# Spine14v1.net
KiCad netlist of a schematic drawn in EAGLE
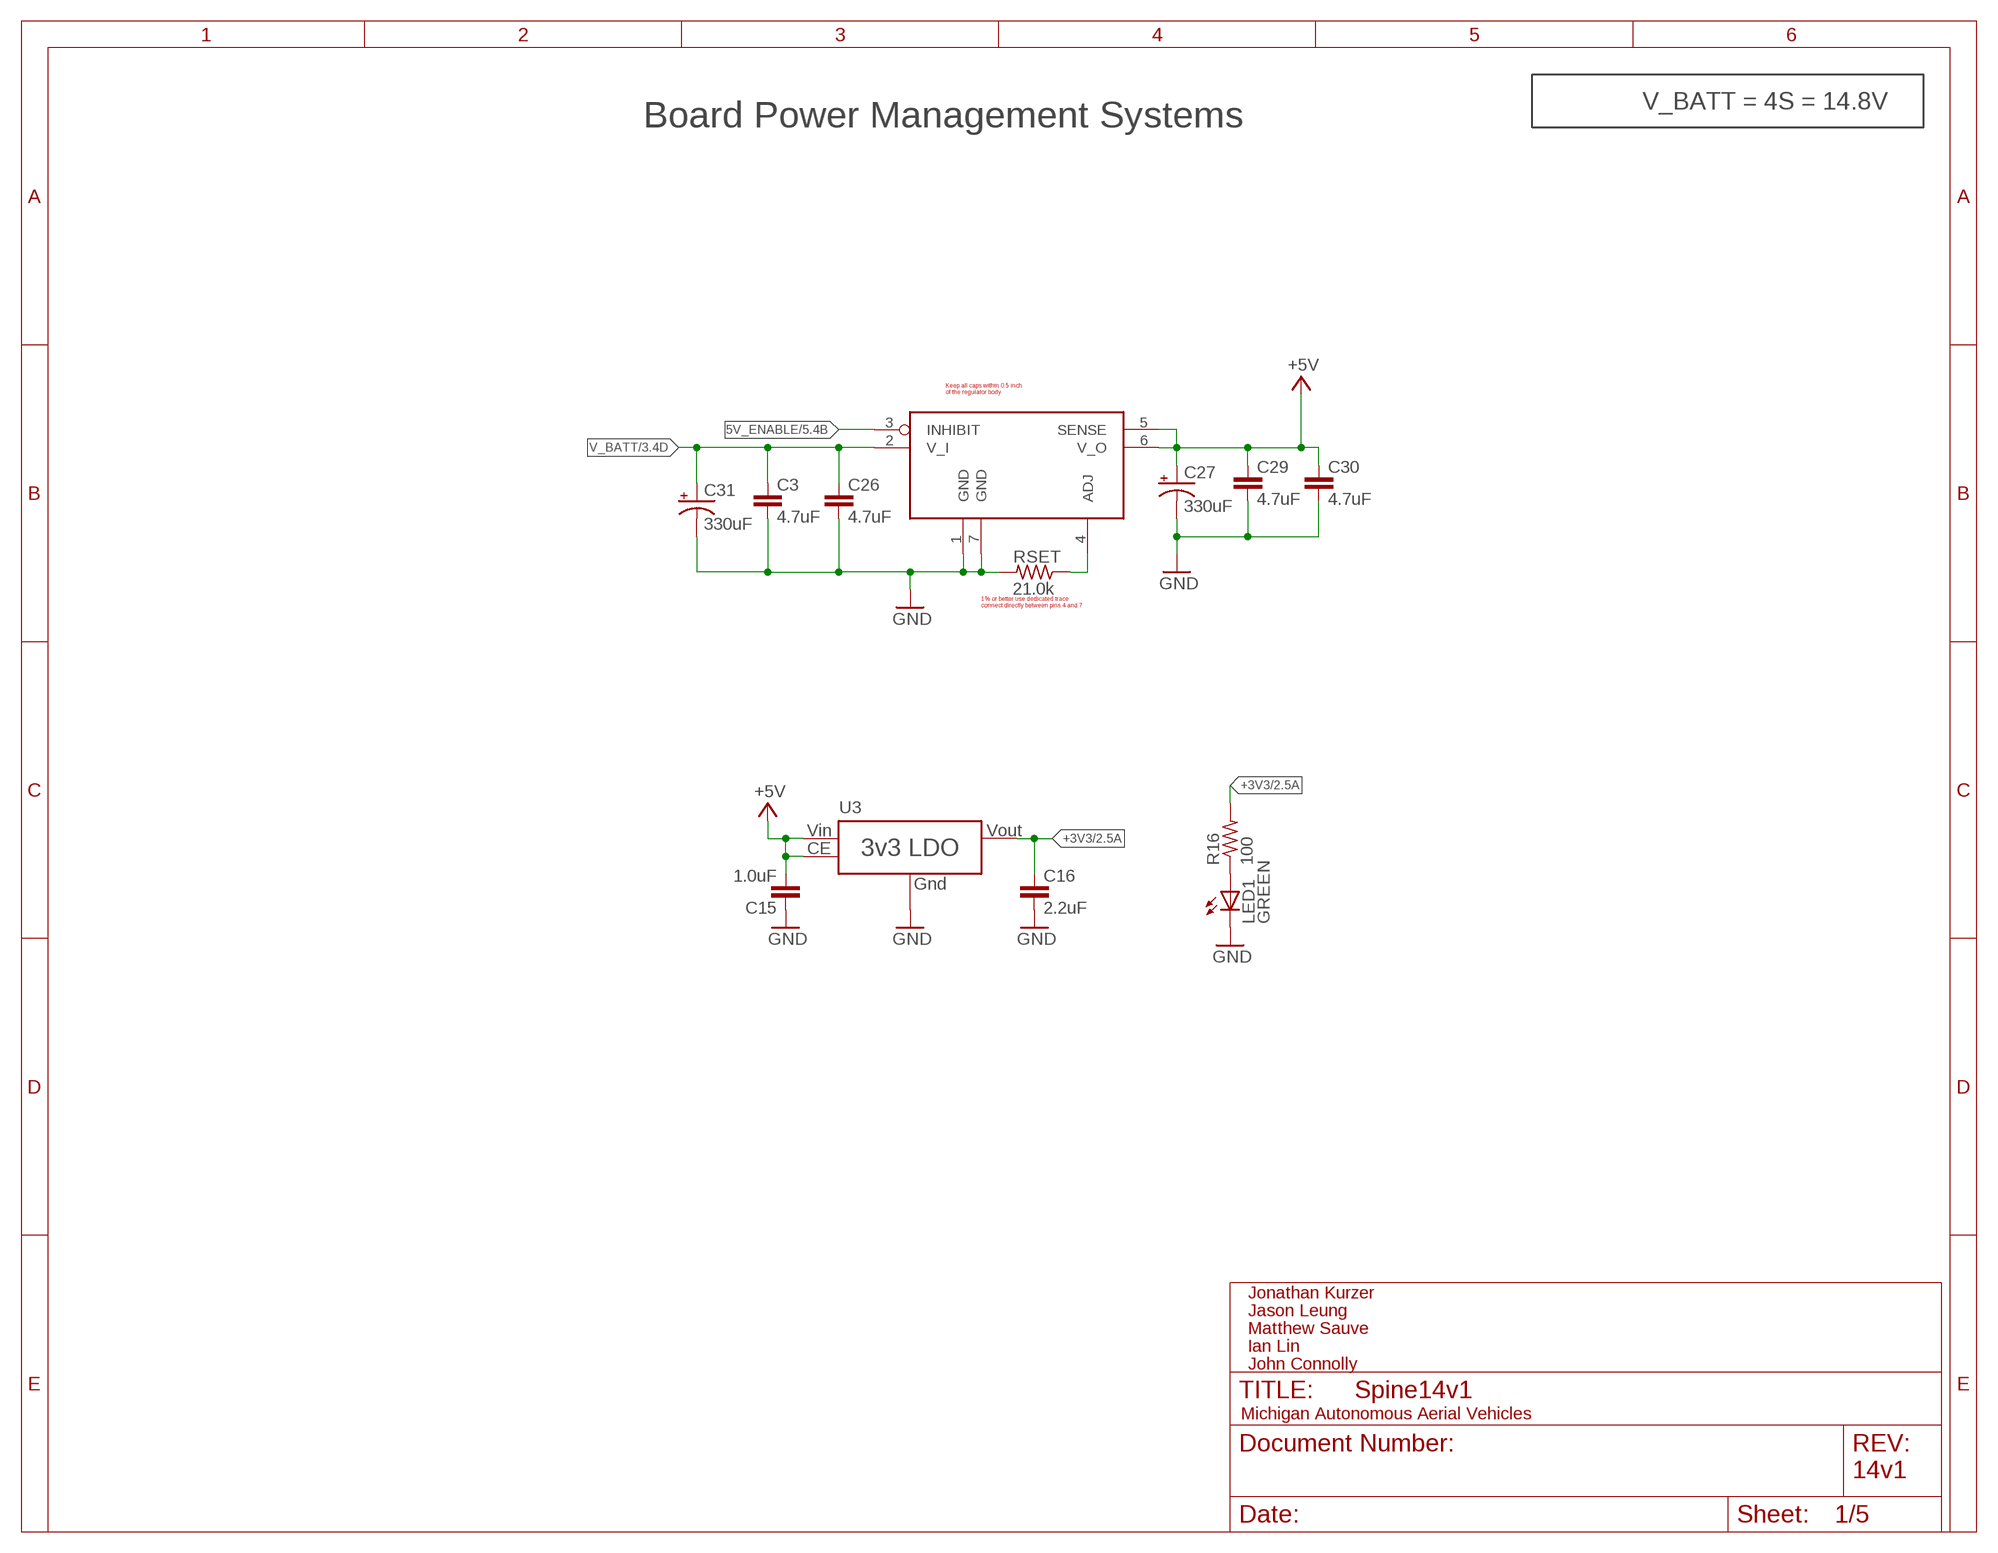
[diagram p0: schematic, sheet 1]
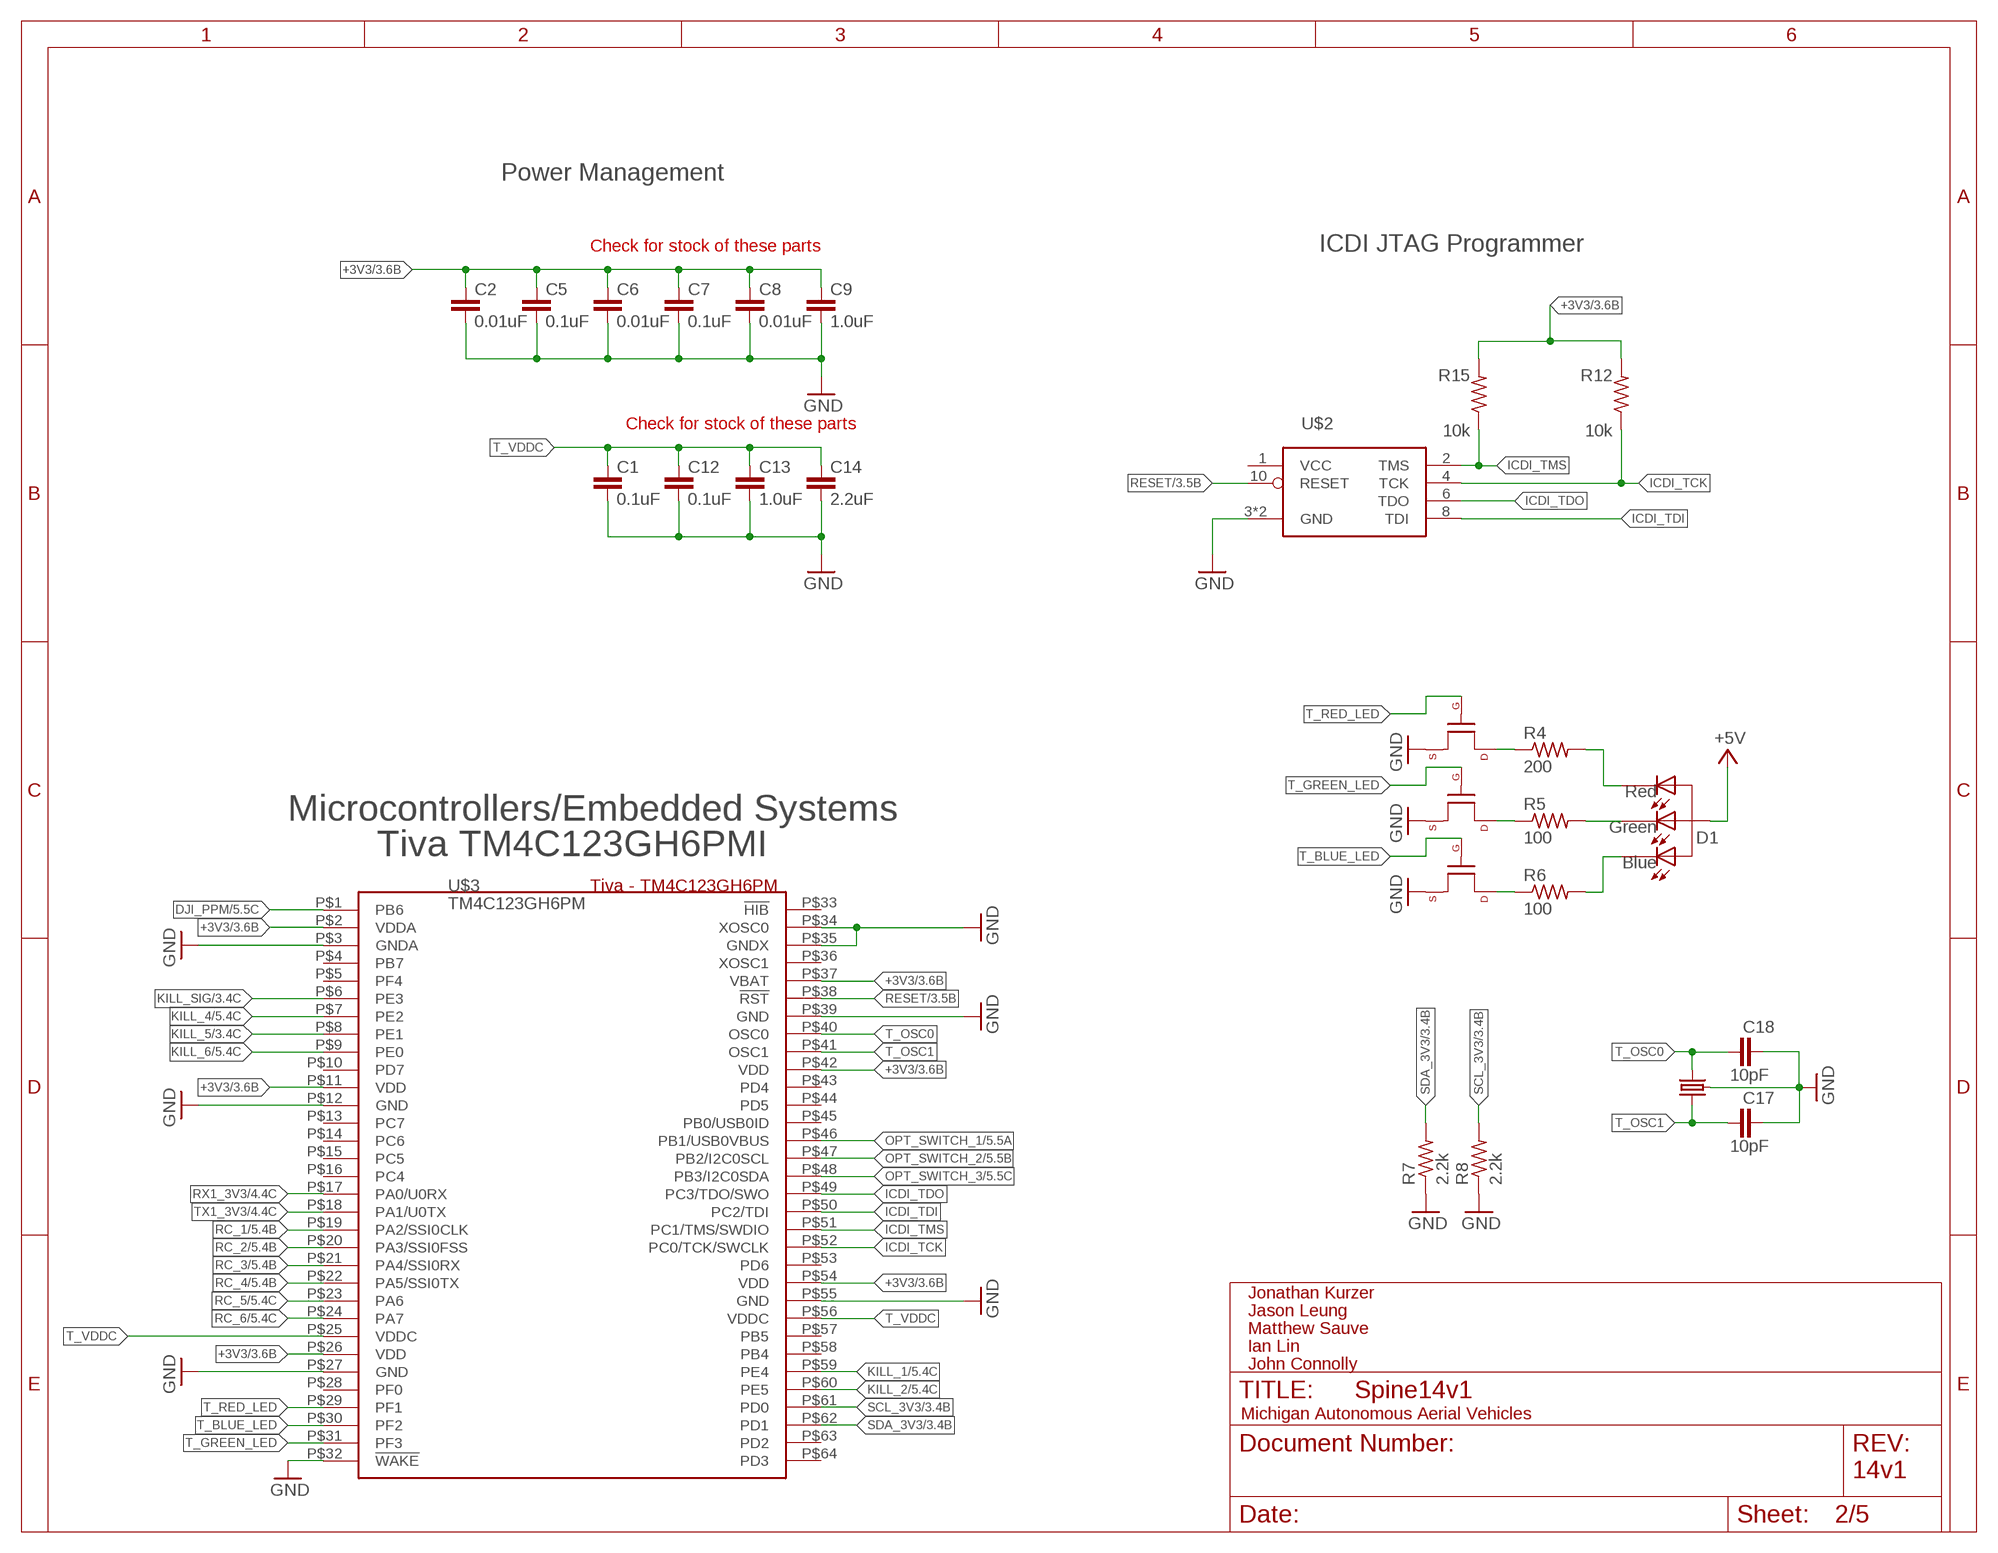
[diagram p1: schematic, sheet 2]
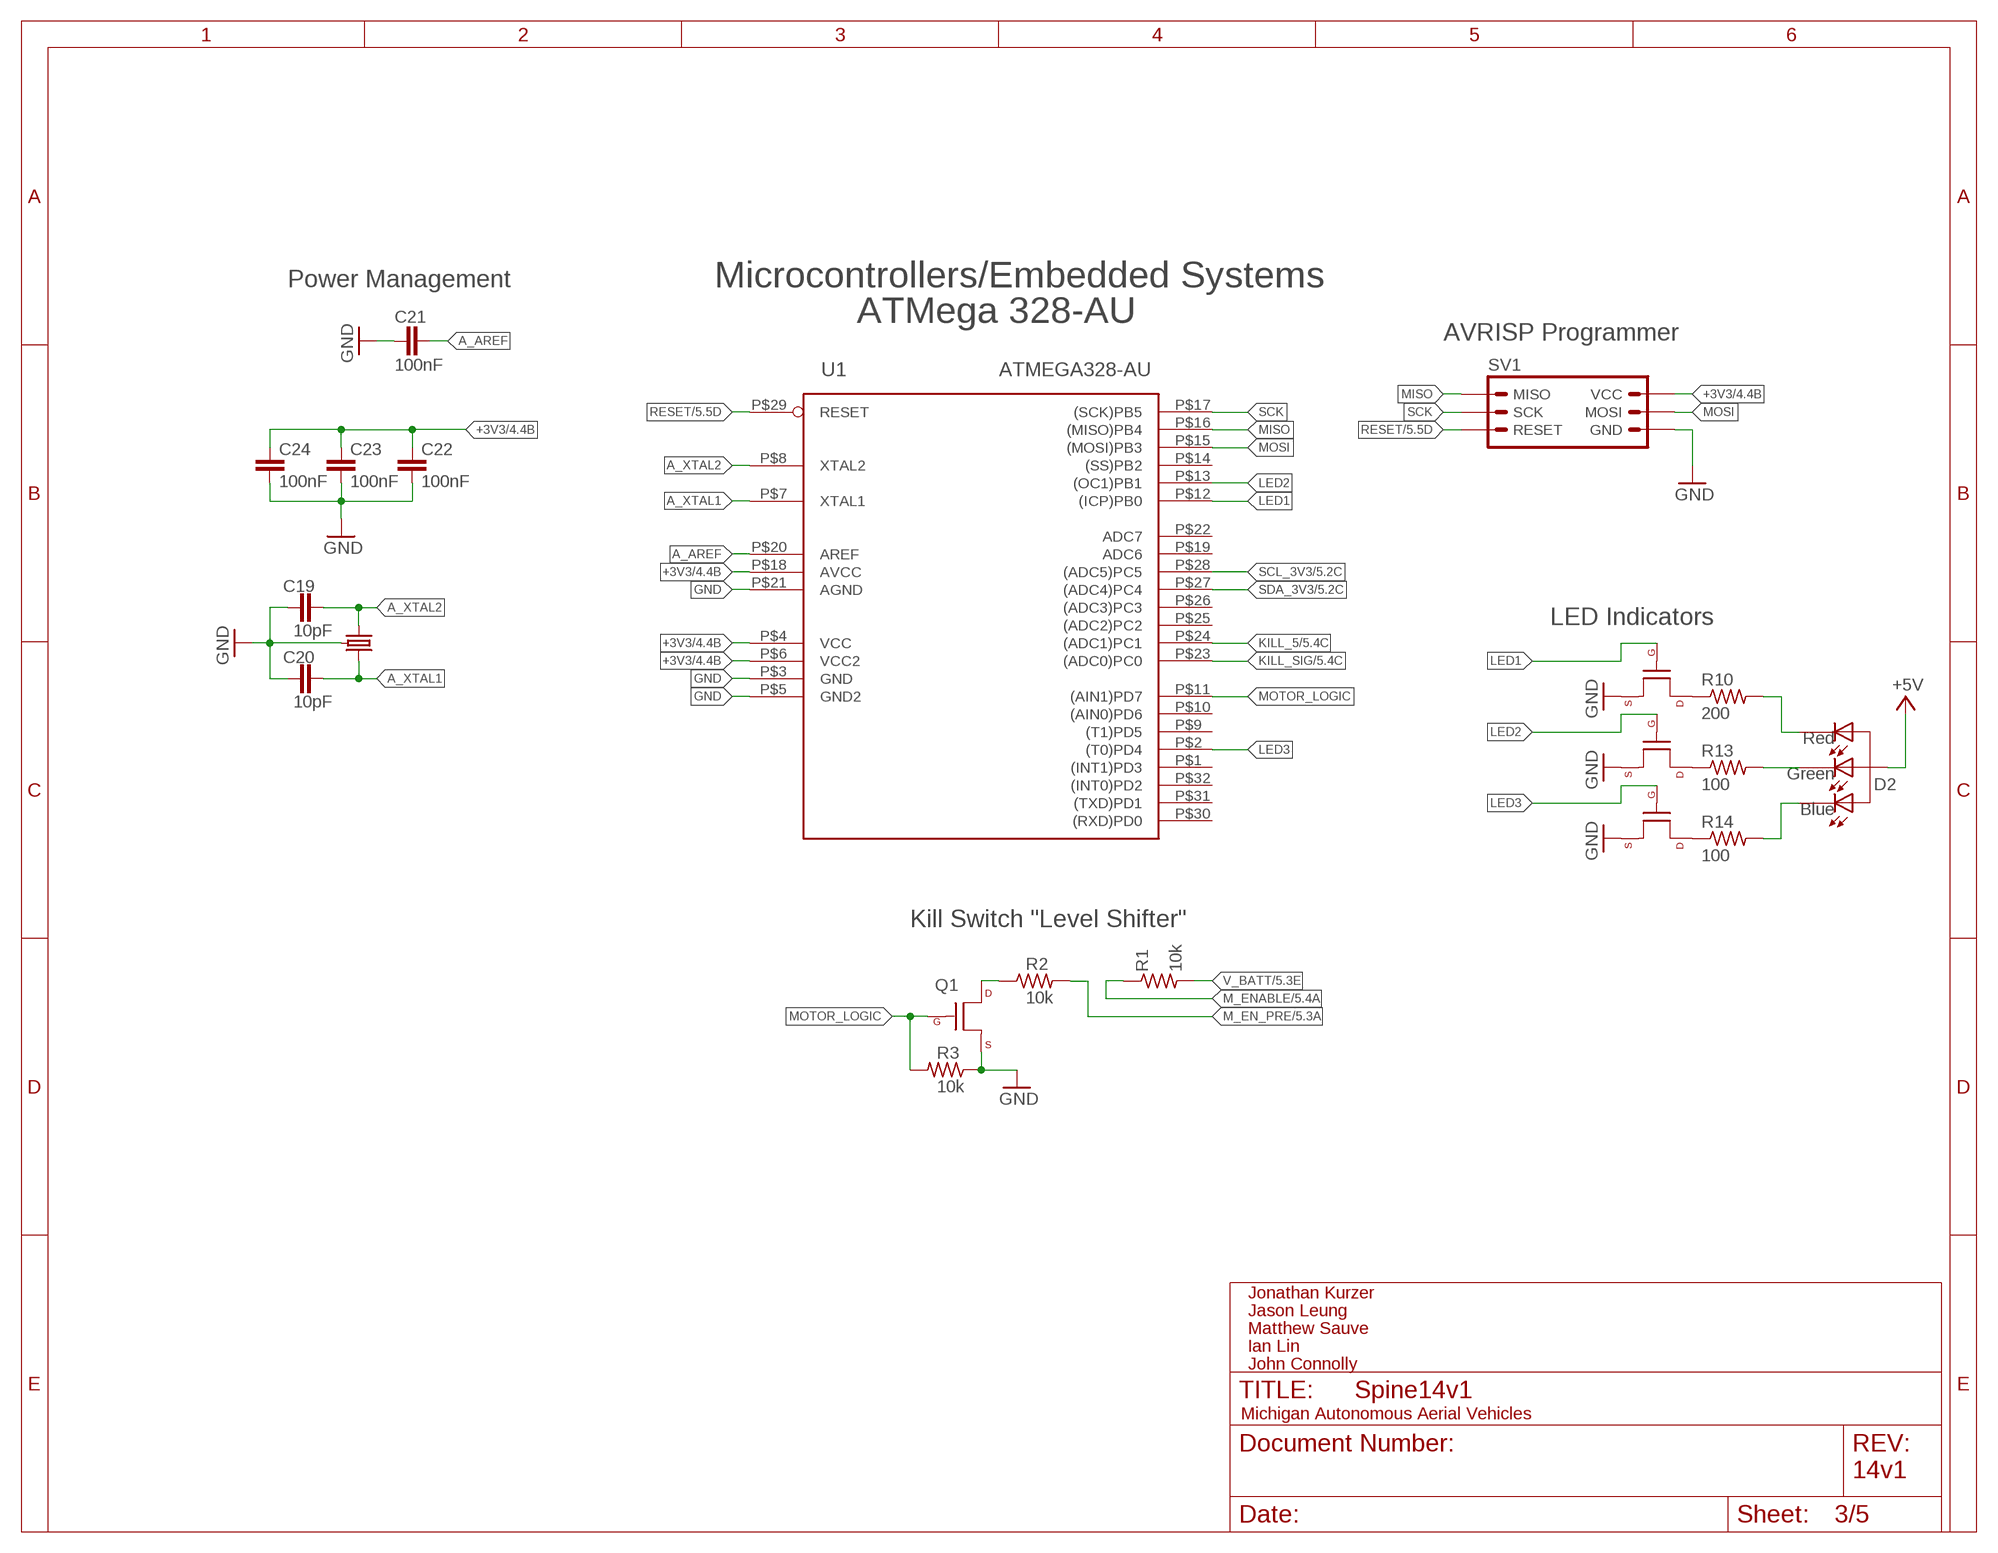
[diagram p2: schematic, sheet 3]
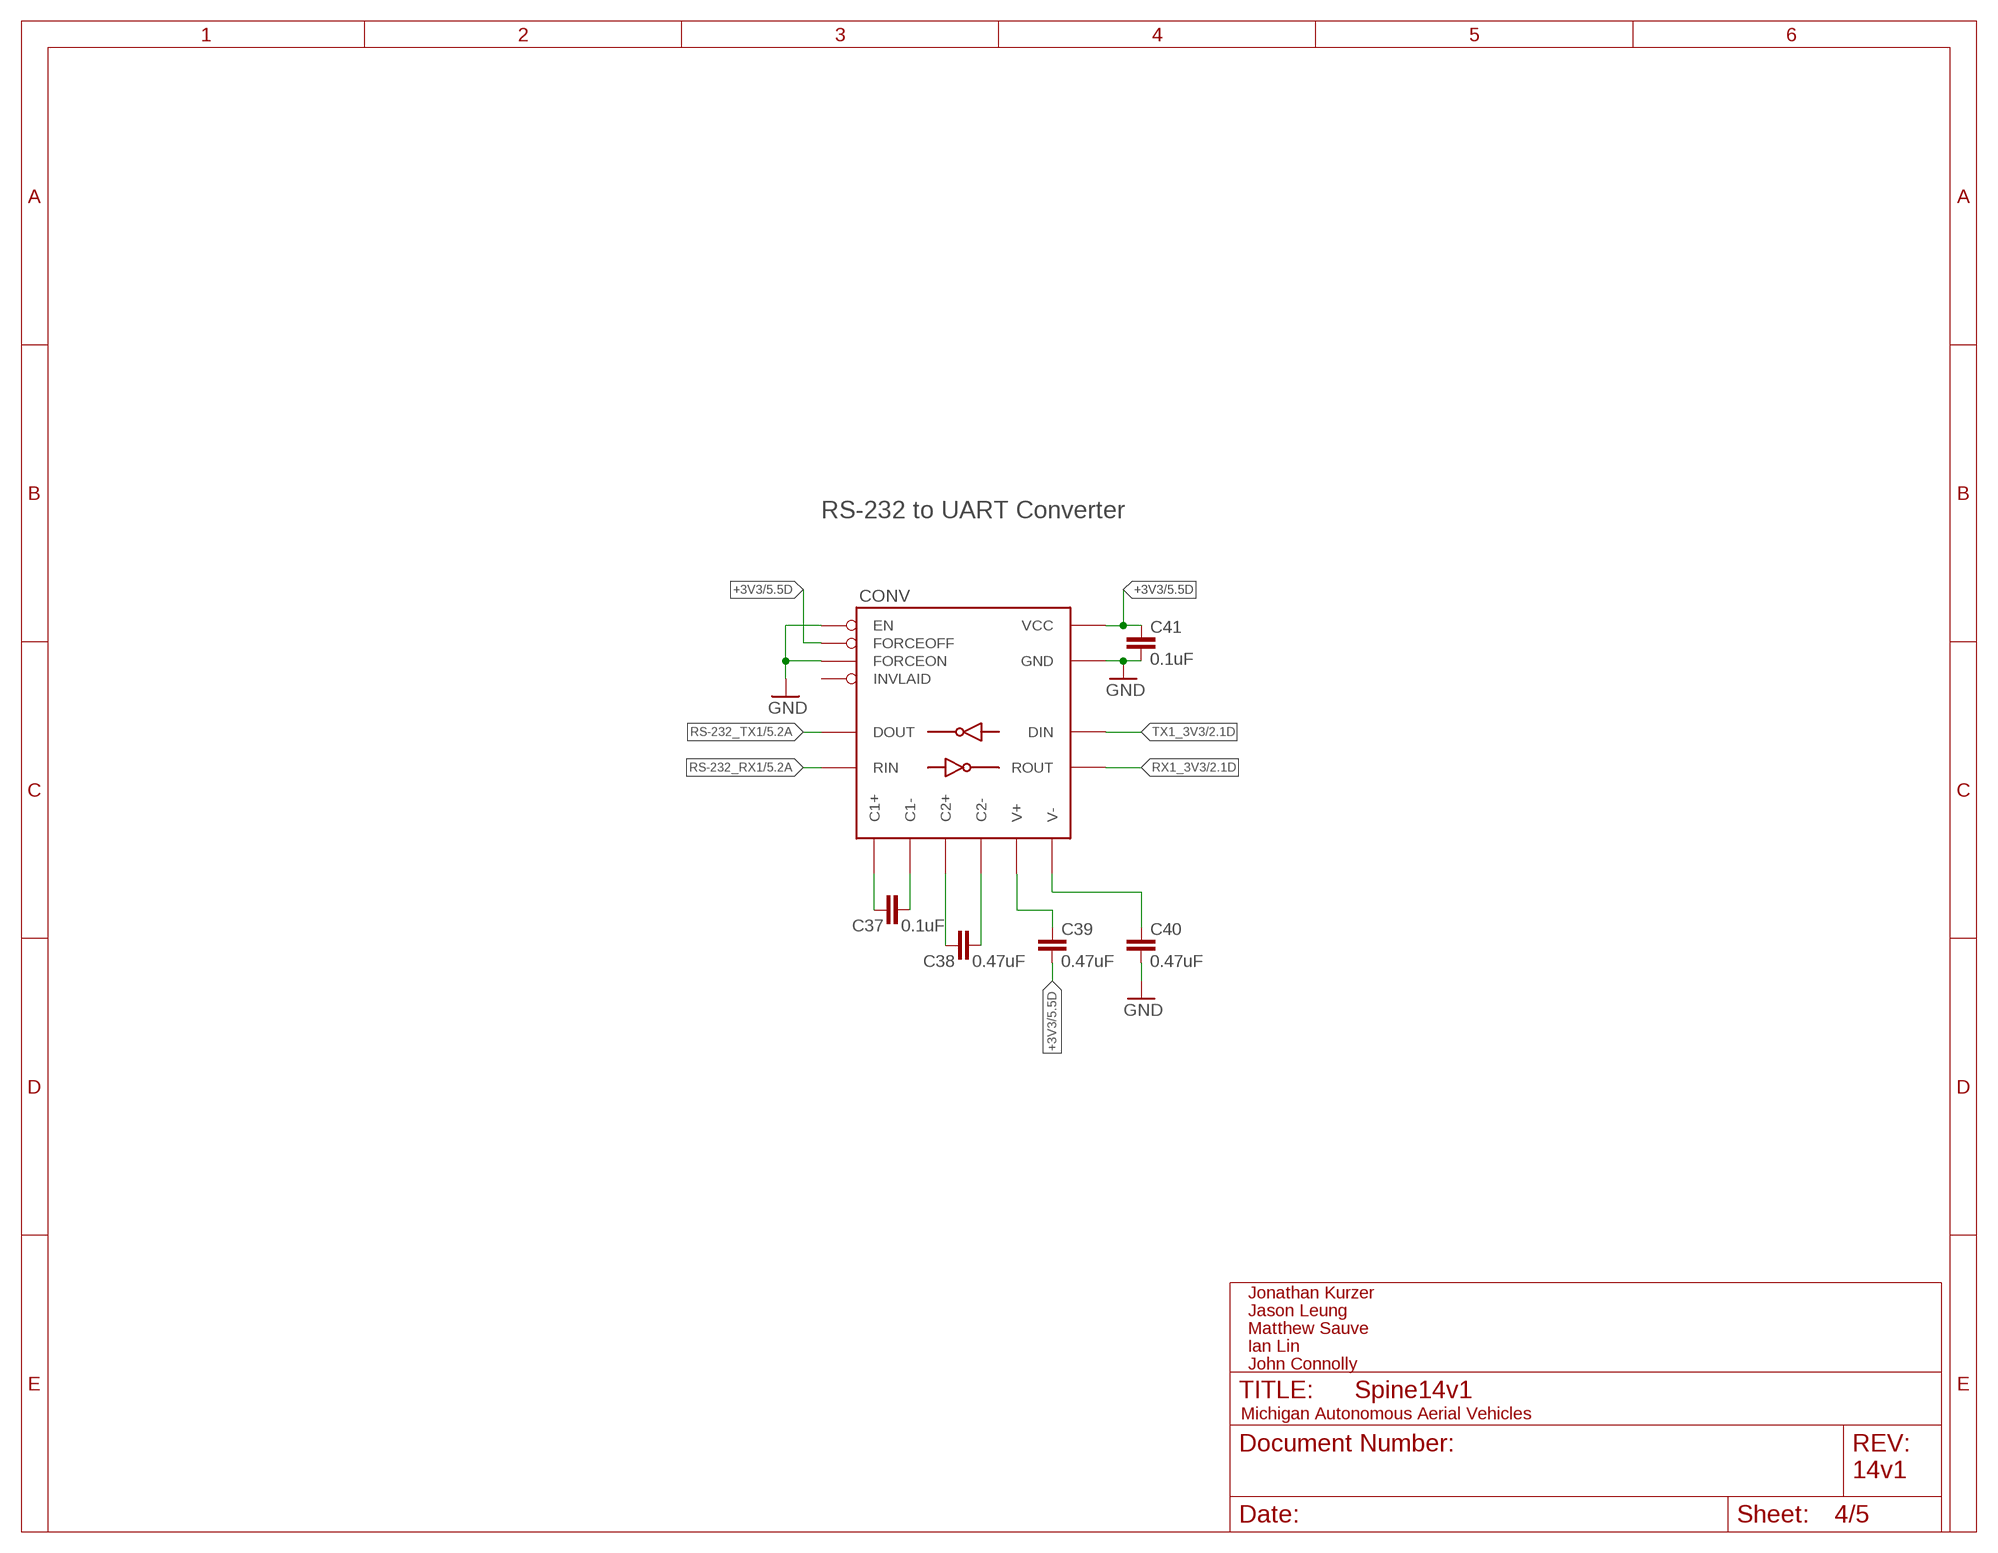
[diagram p3: schematic, sheet 4]
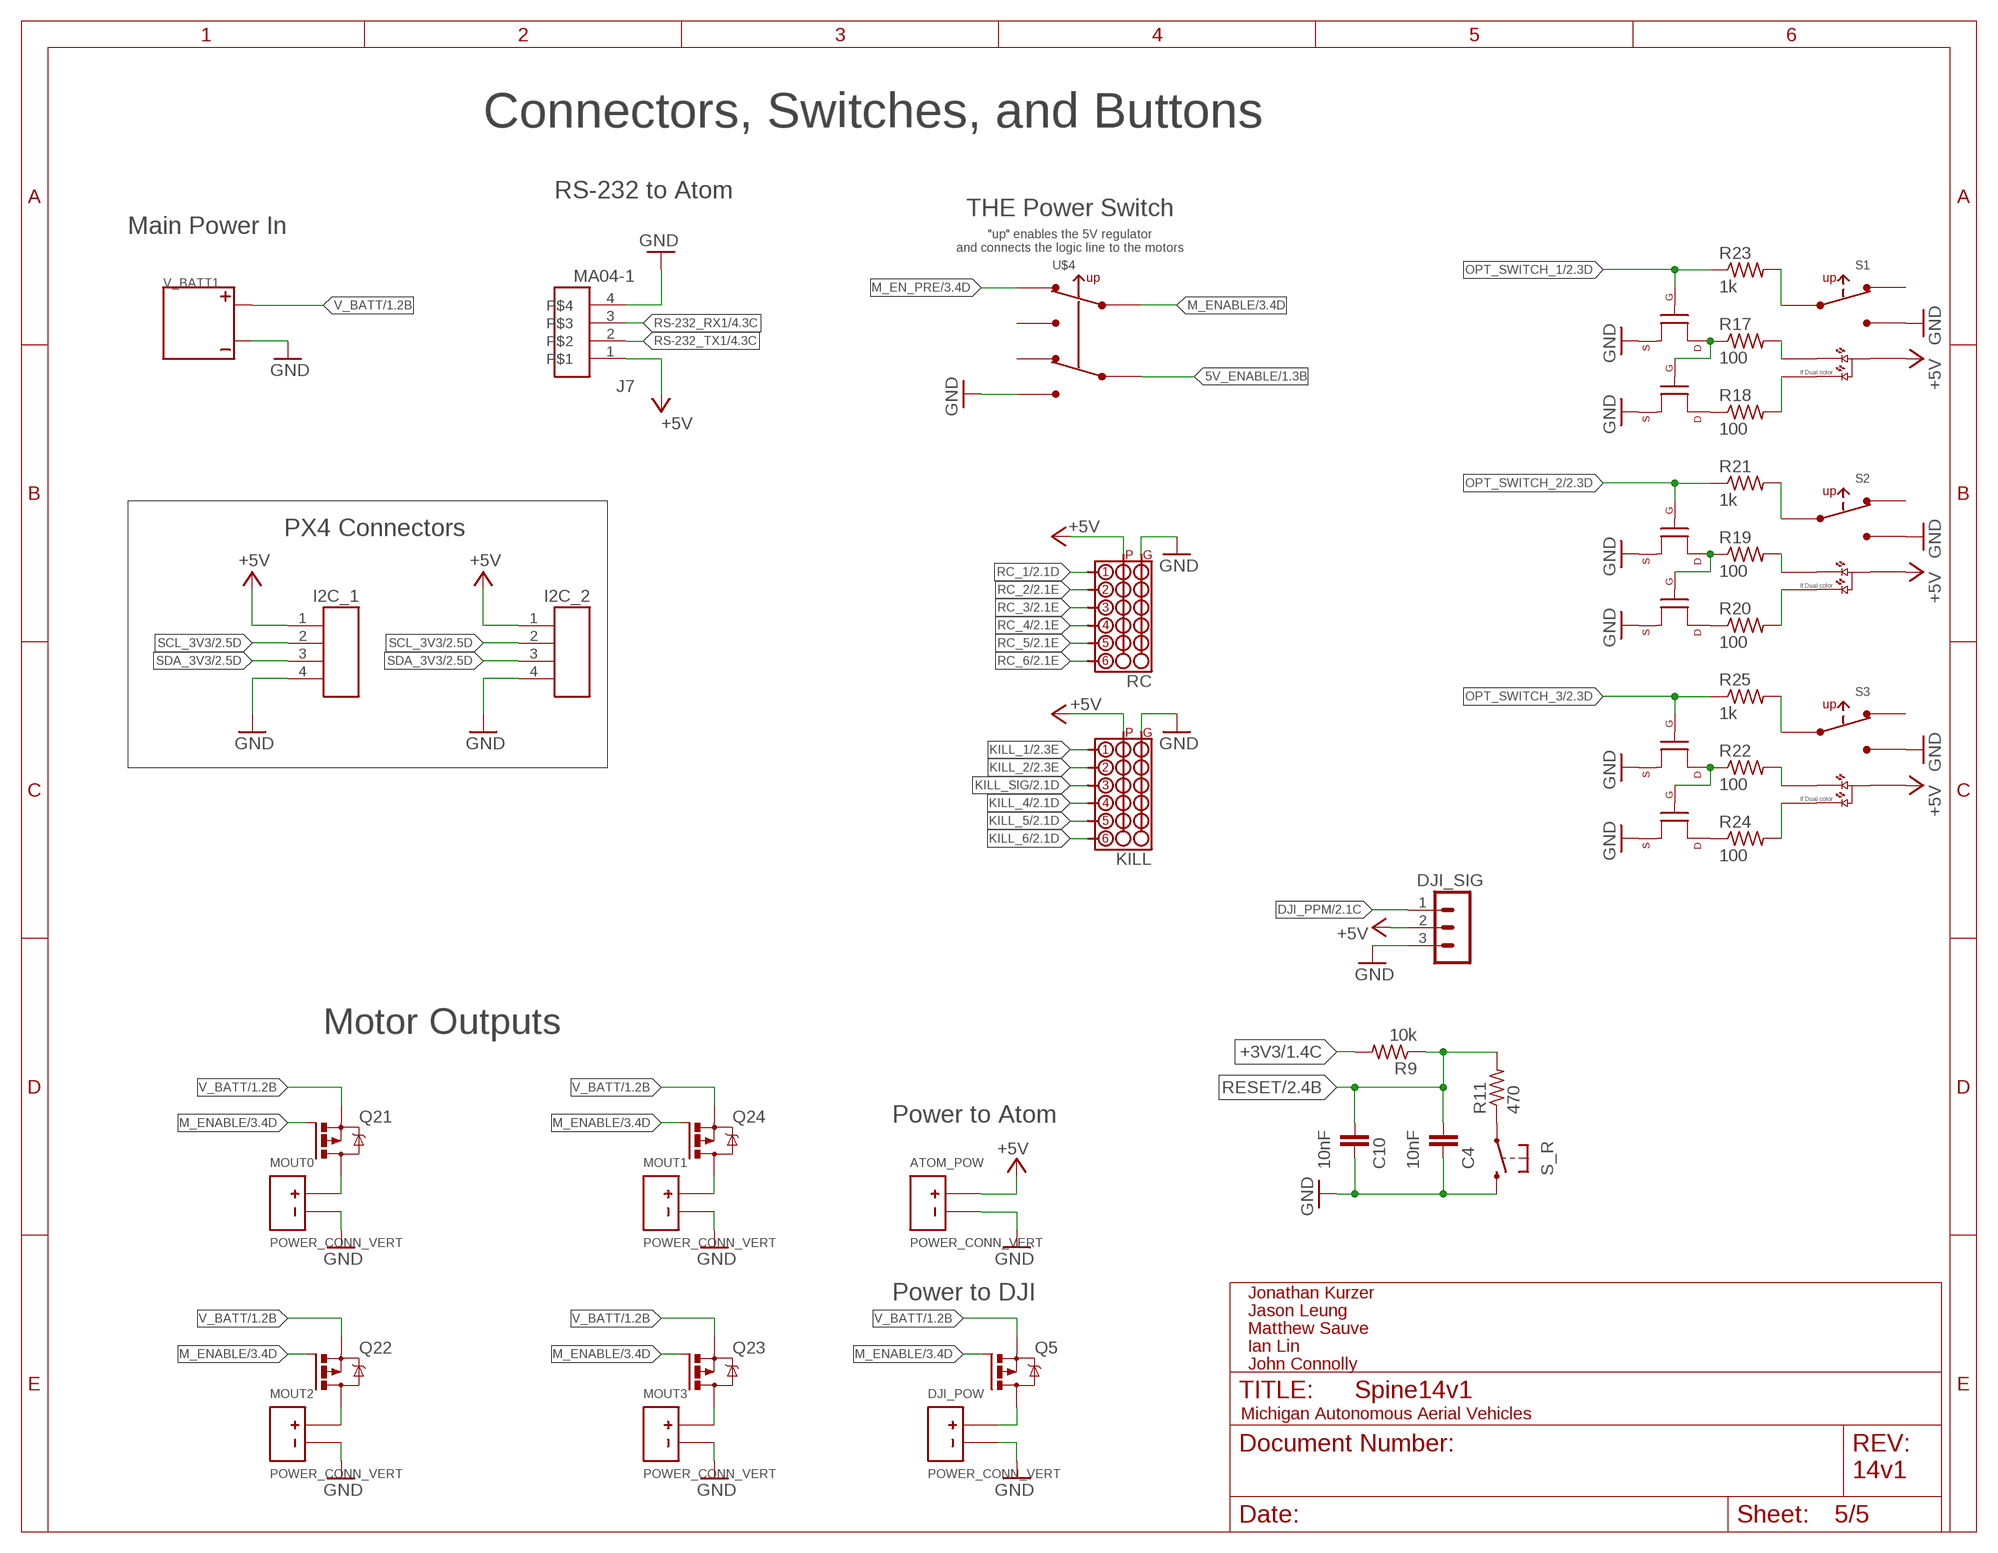
[diagram p4: schematic, sheet 5]

(export (version "E")
  (design (tool "Eeschema 10.0.6"))
  (components
    (comp (ref "C19")
      (value "10pF")
      (footprint "eagle-import:C0603")
      (fields (field (name "DIGIKEY#") "399-1049-1-ND"))
      (libsource (lib "eagle-import") (part "C-EUC0603"))
    )
    (comp (ref "C20")
      (value "10pF")
      (footprint "eagle-import:C0603")
      (fields (field (name "DIGIKEY#") "399-1049-1-ND"))
      (libsource (lib "eagle-import") (part "C-EUC0603"))
    )
    (comp (ref "C21")
      (value "100nF")
      (footprint "eagle-import:C0603")
      (fields (field (name "DIGIKEY#") "1276-1000-1-ND"))
      (libsource (lib "eagle-import") (part "C-EUC0603"))
    )
    (comp (ref "C22")
      (value "100nF")
      (footprint "eagle-import:C0603")
      (fields (field (name "DIGIKEY#") "1276-1000-1-ND"))
      (libsource (lib "eagle-import") (part "C-EUC0603"))
    )
    (comp (ref "C23")
      (value "100nF")
      (footprint "eagle-import:C0603")
      (fields (field (name "DIGIKEY#") "1276-1000-1-ND"))
      (libsource (lib "eagle-import") (part "C-EUC0603"))
    )
    (comp (ref "C24")
      (value "100nF")
      (footprint "eagle-import:C0603")
      (fields (field (name "DIGIKEY#") "1276-1000-1-ND"))
      (libsource (lib "eagle-import") (part "C-EUC0603"))
    )
    (comp (ref "D2")
      (value "LED_RGB_CA")
      (footprint "eagle-import:LED_RGB_0606")
      (libsource (lib "eagle-import") (part "LED_RGB_CA"))
    )
    (comp (ref "Q1")
      (value "MOSFET-NCHANNELSMD")
      (footprint "eagle-import:SOT23-3")
      (libsource (lib "eagle-import") (part "MOSFET-NCHANNELSMD"))
    )
    (comp (ref "Q6")
      (value "MOSFET-NCHANNELSMD")
      (footprint "eagle-import:SOT23-3")
      (libsource (lib "eagle-import") (part "MOSFET-NCHANNELSMD"))
    )
    (comp (ref "Q7")
      (value "MOSFET-NCHANNELSMD")
      (footprint "eagle-import:SOT23-3")
      (libsource (lib "eagle-import") (part "MOSFET-NCHANNELSMD"))
    )
    (comp (ref "Q8")
      (value "MOSFET-NCHANNELSMD")
      (footprint "eagle-import:SOT23-3")
      (libsource (lib "eagle-import") (part "MOSFET-NCHANNELSMD"))
    )
    (comp (ref "R1")
      (value "10k")
      (footprint "eagle-import:R0603")
      (libsource (lib "eagle-import") (part "R-USR0603"))
    )
    (comp (ref "R2")
      (value "10k")
      (footprint "eagle-import:R0603")
      (libsource (lib "eagle-import") (part "R-USR0603"))
    )
    (comp (ref "R3")
      (value "10k")
      (footprint "eagle-import:R0603")
      (libsource (lib "eagle-import") (part "R-USR0603"))
    )
    (comp (ref "R10")
      (value "200")
      (footprint "eagle-import:R0603")
      (libsource (lib "eagle-import") (part "R-USR0603"))
    )
    (comp (ref "R13")
      (value "100")
      (footprint "eagle-import:R0603")
      (libsource (lib "eagle-import") (part "R-USR0603"))
    )
    (comp (ref "R14")
      (value "100")
      (footprint "eagle-import:R0603")
      (libsource (lib "eagle-import") (part "R-USR0603"))
    )
    (comp (ref "SV1")
      (value "AVRISP-6_3X2_PLUG_OF_NAILS")
      (footprint "eagle-import:TC2030-IDC")
      (libsource (lib "eagle-import") (part "AVRISP-6_3X2_PLUG_OF_NAILS"))
    )
    (comp (ref "U$6")
      (value "CRYSTAL_403C11E16")
      (footprint "eagle-import:4-SMD-SWITCH")
      (libsource (lib "eagle-import") (part "CRYSTAL_403C11E16"))
    )
    (comp (ref "U1")
      (value "ATMEGA328-AU")
      (footprint "eagle-import:32-TQFP")
      (libsource (lib "eagle-import") (part "ATMEGA328-AU"))
    )
    (comp (ref "ATOM_POW")
      (value "POWER_CONN_VERT")
      (footprint "eagle-import:POWER_CONN")
      (libsource (lib "eagle-import") (part "POWER_CONN_VERT"))
    )
    (comp (ref "C4")
      (value "10nF")
      (footprint "eagle-import:C0603")
      (libsource (lib "eagle-import") (part "C-EUC0603"))
    )
    (comp (ref "C10")
      (value "10nF")
      (footprint "eagle-import:C0603")
      (libsource (lib "eagle-import") (part "C-EUC0603"))
    )
    (comp (ref "DJI_POW")
      (value "POWER_CONN_VERT")
      (footprint "eagle-import:POWER_CONN")
      (libsource (lib "eagle-import") (part "POWER_CONN_VERT"))
    )
    (comp (ref "DJI_SIG")
      (value "MA03-1")
      (footprint "eagle-import:MA03-1")
      (libsource (lib "eagle-import") (part "MA03-1"))
    )
    (comp (ref "I2C_1")
      (value "CONN_HEADER_4POS_RIGHT_ANGLE_I2C")
      (footprint "eagle-import:CONN_HEADER_4POS_1.25MM_SMD")
      (libsource (lib "eagle-import") (part "CONN_HEADER_4POS_RIGHT_ANGLE_I2C"))
    )
    (comp (ref "I2C_2")
      (value "CONN_HEADER_4POS_RIGHT_ANGLE_I2C")
      (footprint "eagle-import:CONN_HEADER_4POS_1.25MM_SMD")
      (libsource (lib "eagle-import") (part "CONN_HEADER_4POS_RIGHT_ANGLE_I2C"))
    )
    (comp (ref "J7")
      (value "MA04-1")
      (footprint "eagle-import:MA-04-SMD")
      (libsource (lib "eagle-import") (part "MA04-1"))
    )
    (comp (ref "KILL")
      (value "RC_RECIEVER_RECEP")
      (footprint "eagle-import:RC_RECIEVER_RECEP")
      (libsource (lib "eagle-import") (part "RC_RECIEVER_RECEP"))
    )
    (comp (ref "MOUT0")
      (value "POWER_CONN_VERT")
      (footprint "eagle-import:POWER_CONN")
      (libsource (lib "eagle-import") (part "POWER_CONN_VERT"))
    )
    (comp (ref "MOUT1")
      (value "POWER_CONN_VERT")
      (footprint "eagle-import:POWER_CONN")
      (libsource (lib "eagle-import") (part "POWER_CONN_VERT"))
    )
    (comp (ref "MOUT2")
      (value "POWER_CONN_VERT")
      (footprint "eagle-import:POWER_CONN")
      (libsource (lib "eagle-import") (part "POWER_CONN_VERT"))
    )
    (comp (ref "MOUT3")
      (value "POWER_CONN_VERT")
      (footprint "eagle-import:POWER_CONN")
      (libsource (lib "eagle-import") (part "POWER_CONN_VERT"))
    )
    (comp (ref "Q5")
      (value "P-MOSFET-SO8POWER-PAK")
      (footprint "eagle-import:SO-8_POWER-PAK")
      (libsource (lib "eagle-import") (part "P-MOSFET-SO8POWER-PAK"))
    )
    (comp (ref "Q9")
      (value "MOSFET-NCHANNELSMD")
      (footprint "eagle-import:SOT23-3")
      (libsource (lib "eagle-import") (part "MOSFET-NCHANNELSMD"))
    )
    (comp (ref "Q10")
      (value "MOSFET-NCHANNELSMD")
      (footprint "eagle-import:SOT23-3")
      (libsource (lib "eagle-import") (part "MOSFET-NCHANNELSMD"))
    )
    (comp (ref "Q11")
      (value "MOSFET-NCHANNELSMD")
      (footprint "eagle-import:SOT23-3")
      (libsource (lib "eagle-import") (part "MOSFET-NCHANNELSMD"))
    )
    (comp (ref "Q12")
      (value "MOSFET-NCHANNELSMD")
      (footprint "eagle-import:SOT23-3")
      (libsource (lib "eagle-import") (part "MOSFET-NCHANNELSMD"))
    )
    (comp (ref "Q13")
      (value "MOSFET-NCHANNELSMD")
      (footprint "eagle-import:SOT23-3")
      (libsource (lib "eagle-import") (part "MOSFET-NCHANNELSMD"))
    )
    (comp (ref "Q14")
      (value "MOSFET-NCHANNELSMD")
      (footprint "eagle-import:SOT23-3")
      (libsource (lib "eagle-import") (part "MOSFET-NCHANNELSMD"))
    )
    (comp (ref "Q21")
      (value "P-MOSFET-SO8POWER-PAK")
      (footprint "eagle-import:SO-8_POWER-PAK")
      (libsource (lib "eagle-import") (part "P-MOSFET-SO8POWER-PAK"))
    )
    (comp (ref "Q22")
      (value "P-MOSFET-SO8POWER-PAK")
      (footprint "eagle-import:SO-8_POWER-PAK")
      (libsource (lib "eagle-import") (part "P-MOSFET-SO8POWER-PAK"))
    )
    (comp (ref "Q23")
      (value "P-MOSFET-SO8POWER-PAK")
      (footprint "eagle-import:SO-8_POWER-PAK")
      (libsource (lib "eagle-import") (part "P-MOSFET-SO8POWER-PAK"))
    )
    (comp (ref "Q24")
      (value "P-MOSFET-SO8POWER-PAK")
      (footprint "eagle-import:SO-8_POWER-PAK")
      (libsource (lib "eagle-import") (part "P-MOSFET-SO8POWER-PAK"))
    )
    (comp (ref "R9")
      (value "10k")
      (footprint "eagle-import:R0603")
      (libsource (lib "eagle-import") (part "R-USR0603"))
    )
    (comp (ref "R11")
      (value "470")
      (footprint "eagle-import:R0603")
      (libsource (lib "eagle-import") (part "R-USR0603"))
    )
    (comp (ref "R17")
      (value "100")
      (footprint "eagle-import:R0603")
      (libsource (lib "eagle-import") (part "R-USR0603"))
    )
    (comp (ref "R18")
      (value "100")
      (footprint "eagle-import:R0603")
      (libsource (lib "eagle-import") (part "R-USR0603"))
    )
    (comp (ref "R19")
      (value "100")
      (footprint "eagle-import:R0603")
      (libsource (lib "eagle-import") (part "R-USR0603"))
    )
    (comp (ref "R20")
      (value "100")
      (footprint "eagle-import:R0603")
      (libsource (lib "eagle-import") (part "R-USR0603"))
    )
    (comp (ref "R21")
      (value "1k")
      (footprint "eagle-import:R0603")
      (libsource (lib "eagle-import") (part "R-USR0603"))
    )
    (comp (ref "R22")
      (value "100")
      (footprint "eagle-import:R0603")
      (libsource (lib "eagle-import") (part "R-USR0603"))
    )
    (comp (ref "R23")
      (value "1k")
      (footprint "eagle-import:R0603")
      (libsource (lib "eagle-import") (part "R-USR0603"))
    )
    (comp (ref "R24")
      (value "100")
      (footprint "eagle-import:R0603")
      (libsource (lib "eagle-import") (part "R-USR0603"))
    )
    (comp (ref "R25")
      (value "1k")
      (footprint "eagle-import:R0603")
      (libsource (lib "eagle-import") (part "R-USR0603"))
    )
    (comp (ref "RC")
      (value "RC_RECIEVER_RECEP")
      (footprint "eagle-import:RC_RECIEVER_RECEP")
      (libsource (lib "eagle-import") (part "RC_RECIEVER_RECEP"))
    )
    (comp (ref "S1")
      (value "SWITCH_SPDT_ILUMINATED_2COLOR_VERT_ILLUMINATED")
      (footprint "eagle-import:NKK_VERT_SWITCH_6PIN")
      (libsource (lib "eagle-import") (part "SWITCH_SPDT_ILUMINATED_2COLOR_VERT_ILLUMINATED"))
    )
    (comp (ref "S2")
      (value "SWITCH_SPDT_ILUMINATED_2COLOR_VERT_ILLUMINATED")
      (footprint "eagle-import:NKK_VERT_SWITCH_6PIN")
      (libsource (lib "eagle-import") (part "SWITCH_SPDT_ILUMINATED_2COLOR_VERT_ILLUMINATED"))
    )
    (comp (ref "S3")
      (value "SWITCH_SPDT_ILUMINATED_2COLOR_VERT_ILLUMINATED")
      (footprint "eagle-import:NKK_VERT_SWITCH_6PIN")
      (libsource (lib "eagle-import") (part "SWITCH_SPDT_ILUMINATED_2COLOR_VERT_ILLUMINATED"))
    )
    (comp (ref "S_R")
      (value "TACT_BUTTONSMD")
      (footprint "eagle-import:TACT-MOM-SMD")
      (libsource (lib "eagle-import") (part "TACT_BUTTONSMD"))
    )
    (comp (ref "U$4")
      (value "JON_LIB_SWITCH_DPDT")
      (footprint "eagle-import:JON_LIB_SWITCH_VERT_DPDT")
      (libsource (lib "eagle-import") (part "JON_LIB_SWITCH_DPDT"))
    )
    (comp (ref "V_BATT1")
      (value "BATT-CONN-50A_MINI-FIT-SR_THRU-HOLE")
      (footprint "eagle-import:BATT-CONN-50A")
      (libsource (lib "eagle-import") (part "BATT-CONN-50A_MINI-FIT-SR_THRU-HOLE"))
    )
    (comp (ref "C3")
      (value "4.7uF")
      (footprint "eagle-import:C1206")
      (fields (field (name "DIGIKEY#") "587-2994-1-ND"))
      (libsource (lib "eagle-import") (part "C-EUC1206"))
    )
    (comp (ref "C15")
      (value "1.0uF")
      (footprint "eagle-import:C0805")
      (libsource (lib "eagle-import") (part "C-EUC0805"))
    )
    (comp (ref "C16")
      (value "2.2uF")
      (footprint "eagle-import:C0805")
      (libsource (lib "eagle-import") (part "C-EUC0805"))
    )
    (comp (ref "C26")
      (value "4.7uF")
      (footprint "eagle-import:C1206")
      (fields (field (name "DIGIKEY#") "587-2994-1-ND"))
      (libsource (lib "eagle-import") (part "C-EUC1206"))
    )
    (comp (ref "C27")
      (value "330uF")
      (footprint "eagle-import:PANASONIC_F")
      (libsource (lib "eagle-import") (part "CPOL-USF"))
    )
    (comp (ref "C29")
      (value "4.7uF")
      (footprint "eagle-import:C1206")
      (fields (field (name "DIGIKEY#") "587-2994-1-ND"))
      (libsource (lib "eagle-import") (part "C-EUC1206"))
    )
    (comp (ref "C30")
      (value "4.7uF")
      (footprint "eagle-import:C1206")
      (fields (field (name "DIGIKEY#") "587-2994-1-ND"))
      (libsource (lib "eagle-import") (part "C-EUC1206"))
    )
    (comp (ref "C31")
      (value "330uF")
      (footprint "eagle-import:PANASONIC_F")
      (libsource (lib "eagle-import") (part "CPOL-USF"))
    )
    (comp (ref "LED1")
      (value "GREEN")
      (footprint "eagle-import:CHIPLED_0603")
      (libsource (lib "eagle-import") (part "LEDCHIPLED_0603"))
    )
    (comp (ref "R16")
      (value "100")
      (footprint "eagle-import:R0603")
      (libsource (lib "eagle-import") (part "R-USR0603"))
    )
    (comp (ref "RSET")
      (value "21.0k")
      (footprint "eagle-import:R0603")
      (libsource (lib "eagle-import") (part "R-USR0603"))
    )
    (comp (ref "U$5")
      (value "POWER-MODULE-TI-6A_SOLDERLESS_TERMINAL")
      (footprint "eagle-import:POWER-MOD-TI-6A-SOLDERLESS-TERMINAL")
      (libsource (lib "eagle-import") (part "POWER-MODULE-TI-6A_SOLDERLESS_TERMINAL"))
    )
    (comp (ref "U3")
      (value "XC6210")
      (footprint "eagle-import:SOT-25")
      (libsource (lib "eagle-import") (part "XC6210"))
    )
    (comp (ref "C1")
      (value "0.1uF")
      (footprint "eagle-import:C0603")
      (libsource (lib "eagle-import") (part "C-EUC0603"))
    )
    (comp (ref "C2")
      (value "0.01uF")
      (footprint "eagle-import:C0603")
      (libsource (lib "eagle-import") (part "C-EUC0603"))
    )
    (comp (ref "C5")
      (value "0.1uF")
      (footprint "eagle-import:C0603")
      (libsource (lib "eagle-import") (part "C-EUC0603"))
    )
    (comp (ref "C6")
      (value "0.01uF")
      (footprint "eagle-import:C0603")
      (libsource (lib "eagle-import") (part "C-EUC0603"))
    )
    (comp (ref "C7")
      (value "0.1uF")
      (footprint "eagle-import:C0603")
      (libsource (lib "eagle-import") (part "C-EUC0603"))
    )
    (comp (ref "C8")
      (value "0.01uF")
      (footprint "eagle-import:C0603")
      (libsource (lib "eagle-import") (part "C-EUC0603"))
    )
    (comp (ref "C9")
      (value "1.0uF")
      (footprint "eagle-import:C0603")
      (libsource (lib "eagle-import") (part "C-EUC0603"))
    )
    (comp (ref "C12")
      (value "0.1uF")
      (footprint "eagle-import:C0603")
      (libsource (lib "eagle-import") (part "C-EUC0603"))
    )
    (comp (ref "C13")
      (value "1.0uF")
      (footprint "eagle-import:C0805")
      (libsource (lib "eagle-import") (part "C-EUC0805"))
    )
    (comp (ref "C14")
      (value "2.2uF")
      (footprint "eagle-import:C0805")
      (libsource (lib "eagle-import") (part "C-EUC0805"))
    )
    (comp (ref "C17")
      (value "10pF")
      (footprint "eagle-import:C0603")
      (fields (field (name "DIGIKEY#") "399-1049-1-ND"))
      (libsource (lib "eagle-import") (part "C-EUC0603"))
    )
    (comp (ref "C18")
      (value "10pF")
      (footprint "eagle-import:C0603")
      (fields (field (name "DIGIKEY#") "399-1049-1-ND"))
      (libsource (lib "eagle-import") (part "C-EUC0603"))
    )
    (comp (ref "D1")
      (value "LED_RGB_CA")
      (footprint "eagle-import:LED_RGB_0606")
      (libsource (lib "eagle-import") (part "LED_RGB_CA"))
    )
    (comp (ref "Q2")
      (value "MOSFET-NCHANNELSMD")
      (footprint "eagle-import:SOT23-3")
      (libsource (lib "eagle-import") (part "MOSFET-NCHANNELSMD"))
    )
    (comp (ref "Q3")
      (value "MOSFET-NCHANNELSMD")
      (footprint "eagle-import:SOT23-3")
      (libsource (lib "eagle-import") (part "MOSFET-NCHANNELSMD"))
    )
    (comp (ref "Q4")
      (value "MOSFET-NCHANNELSMD")
      (footprint "eagle-import:SOT23-3")
      (libsource (lib "eagle-import") (part "MOSFET-NCHANNELSMD"))
    )
    (comp (ref "R4")
      (value "200")
      (footprint "eagle-import:R0603")
      (libsource (lib "eagle-import") (part "R-USR0603"))
    )
    (comp (ref "R5")
      (value "100")
      (footprint "eagle-import:R0603")
      (libsource (lib "eagle-import") (part "R-USR0603"))
    )
    (comp (ref "R6")
      (value "100")
      (footprint "eagle-import:R0603")
      (libsource (lib "eagle-import") (part "R-USR0603"))
    )
    (comp (ref "R7")
      (value "2.2k")
      (footprint "eagle-import:R0603")
      (libsource (lib "eagle-import") (part "R-USR0603"))
    )
    (comp (ref "R8")
      (value "2.2k")
      (footprint "eagle-import:R0603")
      (libsource (lib "eagle-import") (part "R-USR0603"))
    )
    (comp (ref "R12")
      (value "10k")
      (footprint "eagle-import:R0603")
      (libsource (lib "eagle-import") (part "R-USR0603"))
    )
    (comp (ref "R15")
      (value "10k")
      (footprint "eagle-import:R0603")
      (libsource (lib "eagle-import") (part "R-USR0603"))
    )
    (comp (ref "U$1")
      (value "CRYSTAL_403C11E16")
      (footprint "eagle-import:4-SMD-SWITCH")
      (libsource (lib "eagle-import") (part "CRYSTAL_403C11E16"))
    )
    (comp (ref "U$2")
      (value "JTAG-ARM_TC-10")
      (footprint "eagle-import:TC2050-IDC")
      (libsource (lib "eagle-import") (part "JTAG-ARM_TC-10"))
    )
    (comp (ref "U$3")
      (value "TM4C123GH6PM")
      (footprint "eagle-import:TM4C123GH6PM")
      (libsource (lib "eagle-import") (part "TM4C123GH6PM"))
    )
    (comp (ref "C37")
      (value "0.1uF")
      (footprint "eagle-import:C0603")
      (fields (field (name "DIGIKEY#") "490-1524-1-ND"))
      (libsource (lib "eagle-import") (part "C-EUC0603"))
    )
    (comp (ref "C38")
      (value "0.47uF")
      (footprint "eagle-import:C0805")
      (fields (field (name "DIGIKEY#") "1276-2966-1-ND"))
      (libsource (lib "eagle-import") (part "C-EUC0805"))
    )
    (comp (ref "C39")
      (value "0.47uF")
      (footprint "eagle-import:C0805")
      (fields (field (name "DIGIKEY#") "1276-2966-1-ND"))
      (libsource (lib "eagle-import") (part "C-EUC0805"))
    )
    (comp (ref "C40")
      (value "0.47uF")
      (footprint "eagle-import:C0805")
      (fields (field (name "DIGIKEY#") "1276-2966-1-ND"))
      (libsource (lib "eagle-import") (part "C-EUC0805"))
    )
    (comp (ref "C41")
      (value "0.1uF")
      (footprint "eagle-import:C0603")
      (fields (field (name "DIGIKEY#") "490-1524-1-ND"))
      (libsource (lib "eagle-import") (part "C-EUC0603"))
    )
    (comp (ref "CONV")
      (value "MAX3221-RS232")
      (footprint "eagle-import:16-TSSOP")
      (fields (field (name "DIGIKEY#") "296-19825-1-ND"))
      (libsource (lib "eagle-import") (part "MAX3221-RS232"))
    )
  )
  (nets
    (net (code "1") (name "+3V3") (class "Default")
      (node (ref "C16") (pin "1") (pinfunction "1_1") (pintype "passive"))
      (node (ref "C2") (pin "1") (pinfunction "1_1") (pintype "passive"))
      (node (ref "C22") (pin "1") (pinfunction "1_1") (pintype "passive"))
      (node (ref "C23") (pin "1") (pinfunction "1_1") (pintype "passive"))
      (node (ref "C24") (pin "1") (pinfunction "1_1") (pintype "passive"))
      (node (ref "C39") (pin "2") (pinfunction "2_2") (pintype "passive"))
      (node (ref "C41") (pin "1") (pinfunction "1_1") (pintype "passive"))
      (node (ref "C5") (pin "1") (pinfunction "1_1") (pintype "passive"))
      (node (ref "C6") (pin "1") (pinfunction "1_1") (pintype "passive"))
      (node (ref "C7") (pin "1") (pinfunction "1_1") (pintype "passive"))
      (node (ref "C8") (pin "1") (pinfunction "1_1") (pintype "passive"))
      (node (ref "C9") (pin "1") (pinfunction "1_1") (pintype "passive"))
      (node (ref "CONV") (pin "P$15") (pinfunction "VCC_P$15") (pintype "power_in"))
      (node (ref "CONV") (pin "P$16") (pinfunction "FORCEOFF_P$16") (pintype "input"))
      (node (ref "R12") (pin "2") (pinfunction "2_2") (pintype "passive"))
      (node (ref "R15") (pin "2") (pinfunction "2_2") (pintype "passive"))
      (node (ref "R16") (pin "2") (pinfunction "2_2") (pintype "passive"))
      (node (ref "R9") (pin "2") (pinfunction "2_2") (pintype "passive"))
      (node (ref "SV1") (pin "6") (pinfunction "VCC_6") (pintype "passive"))
      (node (ref "U$3") (pin "P$11") (pinfunction "VDD_P$11") (pintype "bidirectional"))
      (node (ref "U$3") (pin "P$2") (pinfunction "VDDA_P$2") (pintype "bidirectional"))
      (node (ref "U$3") (pin "P$26") (pinfunction "VDD_P$26") (pintype "bidirectional"))
      (node (ref "U$3") (pin "P$37") (pinfunction "VBAT_P$37") (pintype "bidirectional"))
      (node (ref "U$3") (pin "P$42") (pinfunction "VDD_P$42") (pintype "bidirectional"))
      (node (ref "U$3") (pin "P$54") (pinfunction "VDD_P$54") (pintype "bidirectional"))
      (node (ref "U1") (pin "P$18") (pinfunction "AVCC_P$18") (pintype "bidirectional"))
      (node (ref "U1") (pin "P$4") (pinfunction "VCC_P$4") (pintype "bidirectional"))
      (node (ref "U1") (pin "P$6") (pinfunction "VCC2_P$6") (pintype "bidirectional"))
      (node (ref "U3") (pin "5") (pinfunction "VOUT_5") (pintype "power_in"))
    )
    (net (code "2") (name "+5V") (class "Default")
      (node (ref "ATOM_POW") (pin "P1") (pinfunction "P_P1") (pintype "bidirectional"))
      (node (ref "C15") (pin "2") (pinfunction "2_2") (pintype "passive"))
      (node (ref "C27") (pin "+") (pinfunction "+_+") (pintype "passive"))
      (node (ref "C29") (pin "1") (pinfunction "1_1") (pintype "passive"))
      (node (ref "C30") (pin "1") (pinfunction "1_1") (pintype "passive"))
      (node (ref "D1") (pin "1") (pinfunction "A_1") (pintype "passive"))
      (node (ref "D2") (pin "1") (pinfunction "A_1") (pintype "passive"))
      (node (ref "DJI_SIG") (pin "2") (pinfunction "2_2") (pintype "passive"))
      (node (ref "I2C_1") (pin "1") (pinfunction "P$1_1") (pintype "bidirectional"))
      (node (ref "I2C_2") (pin "1") (pinfunction "P$1_1") (pintype "bidirectional"))
      (node (ref "J7") (pin "1") (pinfunction "P$1_1") (pintype "bidirectional"))
      (node (ref "KILL") (pin "VCC") (pinfunction "VCC_VCC") (pintype "bidirectional"))
      (node (ref "KILL") (pin "VCC2") (pinfunction "VCC_VCC2") (pintype "bidirectional"))
      (node (ref "RC") (pin "VCC") (pinfunction "VCC_VCC") (pintype "bidirectional"))
      (node (ref "RC") (pin "VCC2") (pinfunction "VCC_VCC2") (pintype "bidirectional"))
      (node (ref "S1") (pin "P$5") (pinfunction "P$5_P$5") (pintype "bidirectional"))
      (node (ref "S2") (pin "P$5") (pinfunction "P$5_P$5") (pintype "bidirectional"))
      (node (ref "S3") (pin "P$5") (pinfunction "P$5_P$5") (pintype "bidirectional"))
      (node (ref "U$5") (pin "5") (pinfunction "SENSE_5") (pintype "input"))
      (node (ref "U$5") (pin "6") (pinfunction "V_O_6") (pintype "output"))
      (node (ref "U3") (pin "1") (pinfunction "VIN_1") (pintype "power_in"))
      (node (ref "U3") (pin "3") (pinfunction "CE_3") (pintype "input"))
    )
    (net (code "3") (name "5V_ENABLE") (class "Default")
      (node (ref "U$4") (pin "P$5") (pinfunction "P$5_P$5") (pintype "bidirectional"))
      (node (ref "U$5") (pin "3") (pinfunction "INHIBIT_3") (pintype "passive"))
    )
    (net (code "4") (name "A_AREF") (class "Default")
      (node (ref "C21") (pin "1") (pinfunction "1_1") (pintype "passive"))
      (node (ref "U1") (pin "P$20") (pinfunction "AREF_P$20") (pintype "bidirectional"))
    )
    (net (code "5") (name "A_XTAL1") (class "Default")
      (node (ref "C20") (pin "2") (pinfunction "2_2") (pintype "passive"))
      (node (ref "U$6") (pin "3") (pinfunction "2_3") (pintype "bidirectional"))
      (node (ref "U1") (pin "P$7") (pinfunction "XTAL1_P$7") (pintype "bidirectional"))
    )
    (net (code "6") (name "A_XTAL2") (class "Default")
      (node (ref "C19") (pin "2") (pinfunction "2_2") (pintype "passive"))
      (node (ref "U$6") (pin "1") (pinfunction "1_1") (pintype "bidirectional"))
      (node (ref "U1") (pin "P$8") (pinfunction "XTAL2_P$8") (pintype "bidirectional"))
    )
    (net (code "7") (name "DJI_PPM") (class "Default")
      (node (ref "DJI_SIG") (pin "1") (pinfunction "1_1") (pintype "passive"))
      (node (ref "U$3") (pin "P$1") (pinfunction "PB6_P$1") (pintype "bidirectional"))
    )
    (net (code "8") (name "GND") (class "Default")
      (node (ref "ATOM_POW") (pin "P2") (pinfunction "N_P2") (pintype "bidirectional"))
      (node (ref "C1") (pin "2") (pinfunction "2_2") (pintype "passive"))
      (node (ref "C10") (pin "2") (pinfunction "2_2") (pintype "passive"))
      (node (ref "C12") (pin "2") (pinfunction "2_2") (pintype "passive"))
      (node (ref "C13") (pin "2") (pinfunction "2_2") (pintype "passive"))
      (node (ref "C14") (pin "2") (pinfunction "2_2") (pintype "passive"))
      (node (ref "C15") (pin "1") (pinfunction "1_1") (pintype "passive"))
      (node (ref "C16") (pin "2") (pinfunction "2_2") (pintype "passive"))
      (node (ref "C17") (pin "2") (pinfunction "2_2") (pintype "passive"))
      (node (ref "C18") (pin "2") (pinfunction "2_2") (pintype "passive"))
      (node (ref "C19") (pin "1") (pinfunction "1_1") (pintype "passive"))
      (node (ref "C2") (pin "2") (pinfunction "2_2") (pintype "passive"))
      (node (ref "C20") (pin "1") (pinfunction "1_1") (pintype "passive"))
      (node (ref "C21") (pin "2") (pinfunction "2_2") (pintype "passive"))
      (node (ref "C22") (pin "2") (pinfunction "2_2") (pintype "passive"))
      (node (ref "C23") (pin "2") (pinfunction "2_2") (pintype "passive"))
      (node (ref "C24") (pin "2") (pinfunction "2_2") (pintype "passive"))
      (node (ref "C26") (pin "2") (pinfunction "2_2") (pintype "passive"))
      (node (ref "C27") (pin "-") (pinfunction "-_-") (pintype "passive"))
      (node (ref "C29") (pin "2") (pinfunction "2_2") (pintype "passive"))
      (node (ref "C3") (pin "2") (pinfunction "2_2") (pintype "passive"))
      (node (ref "C30") (pin "2") (pinfunction "2_2") (pintype "passive"))
      (node (ref "C31") (pin "-") (pinfunction "-_-") (pintype "passive"))
      (node (ref "C4") (pin "2") (pinfunction "2_2") (pintype "passive"))
      (node (ref "C40") (pin "2") (pinfunction "2_2") (pintype "passive"))
      (node (ref "C41") (pin "2") (pinfunction "2_2") (pintype "passive"))
      (node (ref "C5") (pin "2") (pinfunction "2_2") (pintype "passive"))
      (node (ref "C6") (pin "2") (pinfunction "2_2") (pintype "passive"))
      (node (ref "C7") (pin "2") (pinfunction "2_2") (pintype "passive"))
      (node (ref "C8") (pin "2") (pinfunction "2_2") (pintype "passive"))
      (node (ref "C9") (pin "2") (pinfunction "2_2") (pintype "passive"))
      (node (ref "CONV") (pin "P$1") (pinfunction "EN_P$1") (pintype "input"))
      (node (ref "CONV") (pin "P$12") (pinfunction "FORCEON_P$12") (pintype "input"))
      (node (ref "CONV") (pin "P$14") (pinfunction "GND_P$14") (pintype "power_in"))
      (node (ref "DJI_POW") (pin "P2") (pinfunction "N_P2") (pintype "bidirectional"))
      (node (ref "DJI_SIG") (pin "3") (pinfunction "3_3") (pintype "passive"))
      (node (ref "I2C_1") (pin "4") (pinfunction "P$4_4") (pintype "bidirectional"))
      (node (ref "I2C_2") (pin "4") (pinfunction "P$4_4") (pintype "bidirectional"))
      (node (ref "J7") (pin "4") (pinfunction "P$4_4") (pintype "bidirectional"))
      (node (ref "KILL") (pin "GND") (pinfunction "GND_GND") (pintype "bidirectional"))
      (node (ref "KILL") (pin "GND2") (pinfunction "GND_GND2") (pintype "bidirectional"))
      (node (ref "LED1") (pin "C") (pinfunction "C_C") (pintype "passive"))
      (node (ref "MOUT0") (pin "P2") (pinfunction "N_P2") (pintype "bidirectional"))
      (node (ref "MOUT1") (pin "P2") (pinfunction "N_P2") (pintype "bidirectional"))
      (node (ref "MOUT2") (pin "P2") (pinfunction "N_P2") (pintype "bidirectional"))
      (node (ref "MOUT3") (pin "P2") (pinfunction "N_P2") (pintype "bidirectional"))
      (node (ref "Q1") (pin "2") (pinfunction "S_2") (pintype "passive"))
      (node (ref "Q10") (pin "2") (pinfunction "S_2") (pintype "passive"))
      (node (ref "Q11") (pin "2") (pinfunction "S_2") (pintype "passive"))
      (node (ref "Q12") (pin "2") (pinfunction "S_2") (pintype "passive"))
      (node (ref "Q13") (pin "2") (pinfunction "S_2") (pintype "passive"))
      (node (ref "Q14") (pin "2") (pinfunction "S_2") (pintype "passive"))
      (node (ref "Q2") (pin "2") (pinfunction "S_2") (pintype "passive"))
      (node (ref "Q3") (pin "2") (pinfunction "S_2") (pintype "passive"))
      (node (ref "Q4") (pin "2") (pinfunction "S_2") (pintype "passive"))
      (node (ref "Q6") (pin "2") (pinfunction "S_2") (pintype "passive"))
      (node (ref "Q7") (pin "2") (pinfunction "S_2") (pintype "passive"))
      (node (ref "Q8") (pin "2") (pinfunction "S_2") (pintype "passive"))
      (node (ref "Q9") (pin "2") (pinfunction "S_2") (pintype "passive"))
      (node (ref "R3") (pin "1") (pinfunction "1_1") (pintype "passive"))
      (node (ref "R7") (pin "1") (pinfunction "1_1") (pintype "passive"))
      (node (ref "R8") (pin "1") (pinfunction "1_1") (pintype "passive"))
      (node (ref "RC") (pin "GND") (pinfunction "GND_GND") (pintype "bidirectional"))
      (node (ref "RC") (pin "GND2") (pinfunction "GND_GND2") (pintype "bidirectional"))
      (node (ref "RSET") (pin "2") (pinfunction "2_2") (pintype "passive"))
      (node (ref "S1") (pin "P$1") (pinfunction "P$1_P$1") (pintype "bidirectional"))
      (node (ref "S2") (pin "P$1") (pinfunction "P$1_P$1") (pintype "bidirectional"))
      (node (ref "S3") (pin "P$1") (pinfunction "P$1_P$1") (pintype "bidirectional"))
      (node (ref "SV1") (pin "4") (pinfunction "GND_4") (pintype "passive"))
      (node (ref "S_R") (pin "S") (pinfunction "S_S") (pintype "passive"))
      (node (ref "S_R") (pin "S1") (pinfunction "S_S1") (pintype "passive"))
      (node (ref "U$1") (pin "2") (pinfunction "GND_2") (pintype "bidirectional"))
      (node (ref "U$1") (pin "4") (pinfunction "GND_4") (pintype "bidirectional"))
      (node (ref "U$2") (pin "3") (pinfunction "GND_3") (pintype "bidirectional"))
      (node (ref "U$2") (pin "9") (pinfunction "GND_9") (pintype "bidirectional"))
      (node (ref "U$3") (pin "P$12") (pinfunction "GND_P$12") (pintype "bidirectional"))
      (node (ref "U$3") (pin "P$27") (pinfunction "GND_P$27") (pintype "bidirectional"))
      (node (ref "U$3") (pin "P$3") (pinfunction "GNDA_P$3") (pintype "bidirectional"))
      (node (ref "U$3") (pin "P$32") (pinfunction "~{WAKE}_P$32") (pintype "bidirectional"))
      (node (ref "U$3") (pin "P$34") (pinfunction "XOSC0_P$34") (pintype "bidirectional"))
      (node (ref "U$3") (pin "P$35") (pinfunction "GNDX_P$35") (pintype "bidirectional"))
      (node (ref "U$3") (pin "P$39") (pinfunction "GND_P$39") (pintype "bidirectional"))
      (node (ref "U$3") (pin "P$55") (pinfunction "GND_P$55") (pintype "bidirectional"))
      (node (ref "U$4") (pin "P$6") (pinfunction "P$6_P$6") (pintype "bidirectional"))
      (node (ref "U$5") (pin "1") (pinfunction "GND_1") (pintype "power_in"))
      (node (ref "U$5") (pin "7") (pinfunction "GND_7") (pintype "power_in"))
      (node (ref "U$6") (pin "2") (pinfunction "GND_2") (pintype "bidirectional"))
      (node (ref "U$6") (pin "4") (pinfunction "GND_4") (pintype "bidirectional"))
      (node (ref "U1") (pin "P$21") (pinfunction "AGND_P$21") (pintype "bidirectional"))
      (node (ref "U1") (pin "P$3") (pinfunction "GND_P$3") (pintype "bidirectional"))
      (node (ref "U1") (pin "P$5") (pinfunction "GND2_P$5") (pintype "bidirectional"))
      (node (ref "U3") (pin "2") (pinfunction "GND_2") (pintype "power_in"))
      (node (ref "V_BATT1") (pin "GND-1") (pinfunction "GND_GND-1") (pintype "bidirectional"))
      (node (ref "V_BATT1") (pin "GND-2") (pinfunction "GND_GND-2") (pintype "bidirectional"))
    )
    (net (code "9") (name "ICDI_TCK") (class "Default")
      (node (ref "R12") (pin "1") (pinfunction "1_1") (pintype "passive"))
      (node (ref "U$2") (pin "4") (pinfunction "TCK_4") (pintype "bidirectional"))
      (node (ref "U$3") (pin "P$52") (pinfunction "PC0/TCK/SWCLK_P$52") (pintype "bidirectional"))
    )
    (net (code "10") (name "ICDI_TDI") (class "Default")
      (node (ref "U$2") (pin "8") (pinfunction "TDI_8") (pintype "bidirectional"))
      (node (ref "U$3") (pin "P$50") (pinfunction "PC2/TDI_P$50") (pintype "bidirectional"))
    )
    (net (code "11") (name "ICDI_TDO") (class "Default")
      (node (ref "U$2") (pin "6") (pinfunction "TDO_6") (pintype "bidirectional"))
      (node (ref "U$3") (pin "P$49") (pinfunction "PC3/TDO/SWO_P$49") (pintype "bidirectional"))
    )
    (net (code "12") (name "ICDI_TMS") (class "Default")
      (node (ref "R15") (pin "1") (pinfunction "1_1") (pintype "passive"))
      (node (ref "U$2") (pin "2") (pinfunction "TMS_2") (pintype "bidirectional"))
      (node (ref "U$3") (pin "P$51") (pinfunction "PC1/TMS/SWDIO_P$51") (pintype "bidirectional"))
    )
    (net (code "13") (name "KILL_1") (class "Default")
      (node (ref "KILL") (pin "P$1") (pinfunction "P$1_P$1") (pintype "bidirectional"))
      (node (ref "U$3") (pin "P$59") (pinfunction "PE4_P$59") (pintype "bidirectional"))
    )
    (net (code "14") (name "KILL_2") (class "Default")
      (node (ref "KILL") (pin "P$2") (pinfunction "P$2_P$2") (pintype "bidirectional"))
      (node (ref "U$3") (pin "P$60") (pinfunction "PE5_P$60") (pintype "bidirectional"))
    )
    (net (code "15") (name "KILL_4") (class "Default")
      (node (ref "KILL") (pin "P$4") (pinfunction "P$4_P$4") (pintype "bidirectional"))
      (node (ref "U$3") (pin "P$7") (pinfunction "PE2_P$7") (pintype "bidirectional"))
    )
    (net (code "16") (name "KILL_5") (class "Default")
      (node (ref "KILL") (pin "P$5") (pinfunction "P$5_P$5") (pintype "bidirectional"))
      (node (ref "U$3") (pin "P$8") (pinfunction "PE1_P$8") (pintype "bidirectional"))
      (node (ref "U1") (pin "P$24") (pinfunction "(ADC1)PC1_P$24") (pintype "bidirectional"))
    )
    (net (code "17") (name "KILL_6") (class "Default")
      (node (ref "KILL") (pin "P$6") (pinfunction "P$6_P$6") (pintype "bidirectional"))
      (node (ref "U$3") (pin "P$9") (pinfunction "PE0_P$9") (pintype "bidirectional"))
    )
    (net (code "18") (name "KILL_SIG") (class "Default")
      (node (ref "KILL") (pin "P$3") (pinfunction "P$3_P$3") (pintype "bidirectional"))
      (node (ref "U$3") (pin "P$6") (pinfunction "PE3_P$6") (pintype "bidirectional"))
      (node (ref "U1") (pin "P$23") (pinfunction "(ADC0)PC0_P$23") (pintype "bidirectional"))
    )
    (net (code "19") (name "LED1") (class "Default")
      (node (ref "Q8") (pin "1") (pinfunction "G_1") (pintype "passive"))
      (node (ref "U1") (pin "P$12") (pinfunction "(ICP)PB0_P$12") (pintype "bidirectional"))
    )
    (net (code "20") (name "LED2") (class "Default")
      (node (ref "Q7") (pin "1") (pinfunction "G_1") (pintype "passive"))
      (node (ref "U1") (pin "P$13") (pinfunction "(OC1)PB1_P$13") (pintype "bidirectional"))
    )
    (net (code "21") (name "LED3") (class "Default")
      (node (ref "Q6") (pin "1") (pinfunction "G_1") (pintype "passive"))
      (node (ref "U1") (pin "P$2") (pinfunction "(T0)PD4_P$2") (pintype "bidirectional"))
    )
    (net (code "22") (name "MISO") (class "Default")
      (node (ref "SV1") (pin "1") (pinfunction "MISO_1") (pintype "passive"))
      (node (ref "U1") (pin "P$16") (pinfunction "(MISO)PB4_P$16") (pintype "bidirectional"))
    )
    (net (code "23") (name "MOSI") (class "Default")
      (node (ref "SV1") (pin "5") (pinfunction "MOSI_5") (pintype "passive"))
      (node (ref "U1") (pin "P$15") (pinfunction "(MOSI)PB3_P$15") (pintype "bidirectional"))
    )
    (net (code "24") (name "MOTOR_LOGIC") (class "Default")
      (node (ref "Q1") (pin "1") (pinfunction "G_1") (pintype "passive"))
      (node (ref "R3") (pin "2") (pinfunction "2_2") (pintype "passive"))
      (node (ref "U1") (pin "P$11") (pinfunction "(AIN1)PD7_P$11") (pintype "bidirectional"))
    )
    (net (code "25") (name "M_ENABLE") (class "Default")
      (node (ref "Q21") (pin "G") (pinfunction "G_G") (pintype "passive"))
      (node (ref "Q22") (pin "G") (pinfunction "G_G") (pintype "passive"))
      (node (ref "Q23") (pin "G") (pinfunction "G_G") (pintype "passive"))
      (node (ref "Q24") (pin "G") (pinfunction "G_G") (pintype "passive"))
      (node (ref "Q5") (pin "G") (pinfunction "G_G") (pintype "passive"))
      (node (ref "R1") (pin "1") (pinfunction "1_1") (pintype "passive"))
      (node (ref "U$4") (pin "P$2") (pinfunction "P$2_P$2") (pintype "bidirectional"))
    )
    (net (code "26") (name "M_EN_PRE") (class "Default")
      (node (ref "R2") (pin "2") (pinfunction "2_2") (pintype "passive"))
      (node (ref "U$4") (pin "P$1") (pinfunction "P$1_P$1") (pintype "bidirectional"))
    )
    (net (code "27") (name "Net-(CONV-C1+)") (class "Default")
      (node (ref "C37") (pin "1") (pinfunction "1_1") (pintype "passive"))
      (node (ref "CONV") (pin "P$2") (pinfunction "C1+_P$2") (pintype "passive"))
    )
    (net (code "28") (name "Net-(CONV-C1-)") (class "Default")
      (node (ref "C37") (pin "2") (pinfunction "2_2") (pintype "passive"))
      (node (ref "CONV") (pin "P$4") (pinfunction "C1-_P$4") (pintype "passive"))
    )
    (net (code "29") (name "Net-(CONV-C2+)") (class "Default")
      (node (ref "C38") (pin "1") (pinfunction "1_1") (pintype "passive"))
      (node (ref "CONV") (pin "P$5") (pinfunction "C2+_P$5") (pintype "passive"))
    )
    (net (code "30") (name "Net-(CONV-C2-)") (class "Default")
      (node (ref "C38") (pin "2") (pinfunction "2_2") (pintype "passive"))
      (node (ref "CONV") (pin "P$6") (pinfunction "C2-_P$6") (pintype "passive"))
    )
    (net (code "31") (name "Net-(CONV-V+)") (class "Default")
      (node (ref "C39") (pin "1") (pinfunction "1_1") (pintype "passive"))
      (node (ref "CONV") (pin "P$3") (pinfunction "V+_P$3") (pintype "passive"))
    )
    (net (code "32") (name "Net-(CONV-V-)") (class "Default")
      (node (ref "C40") (pin "1") (pinfunction "1_1") (pintype "passive"))
      (node (ref "CONV") (pin "P$7") (pinfunction "V-_P$7") (pintype "passive"))
    )
    (net (code "33") (name "Net-(D1-B)") (class "Default")
      (node (ref "D1") (pin "4") (pinfunction "B_4") (pintype "passive"))
      (node (ref "R6") (pin "2") (pinfunction "2_2") (pintype "passive"))
    )
    (net (code "34") (name "Net-(D1-G)") (class "Default")
      (node (ref "D1") (pin "3") (pinfunction "G_3") (pintype "passive"))
      (node (ref "R5") (pin "2") (pinfunction "2_2") (pintype "passive"))
    )
    (net (code "35") (name "Net-(D1-R)") (class "Default")
      (node (ref "D1") (pin "2") (pinfunction "R_2") (pintype "passive"))
      (node (ref "R4") (pin "2") (pinfunction "2_2") (pintype "passive"))
    )
    (net (code "36") (name "Net-(D2-B)") (class "Default")
      (node (ref "D2") (pin "4") (pinfunction "B_4") (pintype "passive"))
      (node (ref "R14") (pin "2") (pinfunction "2_2") (pintype "passive"))
    )
    (net (code "37") (name "Net-(D2-G)") (class "Default")
      (node (ref "D2") (pin "3") (pinfunction "G_3") (pintype "passive"))
      (node (ref "R13") (pin "2") (pinfunction "2_2") (pintype "passive"))
    )
    (net (code "38") (name "Net-(D2-R)") (class "Default")
      (node (ref "D2") (pin "2") (pinfunction "R_2") (pintype "passive"))
      (node (ref "R10") (pin "2") (pinfunction "2_2") (pintype "passive"))
    )
    (net (code "39") (name "Net-(DJI_POW-P)") (class "Default")
      (node (ref "DJI_POW") (pin "P1") (pinfunction "P_P1") (pintype "bidirectional"))
      (node (ref "Q5") (pin "D1") (pinfunction "D1_D1") (pintype "passive"))
      (node (ref "Q5") (pin "D2") (pinfunction "D1_D2") (pintype "passive"))
      (node (ref "Q5") (pin "D3") (pinfunction "D1_D3") (pintype "passive"))
      (node (ref "Q5") (pin "D4") (pinfunction "D1_D4") (pintype "passive"))
      (node (ref "Q5") (pin "D5") (pinfunction "D1_D5") (pintype "passive"))
    )
    (net (code "40") (name "Net-(LED1-PadA)") (class "Default")
      (node (ref "LED1") (pin "A") (pinfunction "A_A") (pintype "passive"))
      (node (ref "R16") (pin "1") (pinfunction "1_1") (pintype "passive"))
    )
    (net (code "41") (name "Net-(MOUT0-P)") (class "Default")
      (node (ref "MOUT0") (pin "P1") (pinfunction "P_P1") (pintype "bidirectional"))
      (node (ref "Q21") (pin "D1") (pinfunction "D1_D1") (pintype "passive"))
      (node (ref "Q21") (pin "D2") (pinfunction "D1_D2") (pintype "passive"))
      (node (ref "Q21") (pin "D3") (pinfunction "D1_D3") (pintype "passive"))
      (node (ref "Q21") (pin "D4") (pinfunction "D1_D4") (pintype "passive"))
      (node (ref "Q21") (pin "D5") (pinfunction "D1_D5") (pintype "passive"))
    )
    (net (code "42") (name "Net-(MOUT1-P)") (class "Default")
      (node (ref "MOUT1") (pin "P1") (pinfunction "P_P1") (pintype "bidirectional"))
      (node (ref "Q24") (pin "D1") (pinfunction "D1_D1") (pintype "passive"))
      (node (ref "Q24") (pin "D2") (pinfunction "D1_D2") (pintype "passive"))
      (node (ref "Q24") (pin "D3") (pinfunction "D1_D3") (pintype "passive"))
      (node (ref "Q24") (pin "D4") (pinfunction "D1_D4") (pintype "passive"))
      (node (ref "Q24") (pin "D5") (pinfunction "D1_D5") (pintype "passive"))
    )
    (net (code "43") (name "Net-(MOUT2-P)") (class "Default")
      (node (ref "MOUT2") (pin "P1") (pinfunction "P_P1") (pintype "bidirectional"))
      (node (ref "Q22") (pin "D1") (pinfunction "D1_D1") (pintype "passive"))
      (node (ref "Q22") (pin "D2") (pinfunction "D1_D2") (pintype "passive"))
      (node (ref "Q22") (pin "D3") (pinfunction "D1_D3") (pintype "passive"))
      (node (ref "Q22") (pin "D4") (pinfunction "D1_D4") (pintype "passive"))
      (node (ref "Q22") (pin "D5") (pinfunction "D1_D5") (pintype "passive"))
    )
    (net (code "44") (name "Net-(MOUT3-P)") (class "Default")
      (node (ref "MOUT3") (pin "P1") (pinfunction "P_P1") (pintype "bidirectional"))
      (node (ref "Q23") (pin "D1") (pinfunction "D1_D1") (pintype "passive"))
      (node (ref "Q23") (pin "D2") (pinfunction "D1_D2") (pintype "passive"))
      (node (ref "Q23") (pin "D3") (pinfunction "D1_D3") (pintype "passive"))
      (node (ref "Q23") (pin "D4") (pinfunction "D1_D4") (pintype "passive"))
      (node (ref "Q23") (pin "D5") (pinfunction "D1_D5") (pintype "passive"))
    )
    (net (code "45") (name "Net-(Q1-D)") (class "Default")
      (node (ref "Q1") (pin "3") (pinfunction "D_3") (pintype "passive"))
      (node (ref "R2") (pin "1") (pinfunction "1_1") (pintype "passive"))
    )
    (net (code "46") (name "Net-(Q2-D)") (class "Default")
      (node (ref "Q2") (pin "3") (pinfunction "D_3") (pintype "passive"))
      (node (ref "R6") (pin "1") (pinfunction "1_1") (pintype "passive"))
    )
    (net (code "47") (name "Net-(Q3-D)") (class "Default")
      (node (ref "Q3") (pin "3") (pinfunction "D_3") (pintype "passive"))
      (node (ref "R5") (pin "1") (pinfunction "1_1") (pintype "passive"))
    )
    (net (code "48") (name "Net-(Q4-D)") (class "Default")
      (node (ref "Q4") (pin "3") (pinfunction "D_3") (pintype "passive"))
      (node (ref "R4") (pin "1") (pinfunction "1_1") (pintype "passive"))
    )
    (net (code "49") (name "Net-(Q6-D)") (class "Default")
      (node (ref "Q6") (pin "3") (pinfunction "D_3") (pintype "passive"))
      (node (ref "R14") (pin "1") (pinfunction "1_1") (pintype "passive"))
    )
    (net (code "50") (name "Net-(Q7-D)") (class "Default")
      (node (ref "Q7") (pin "3") (pinfunction "D_3") (pintype "passive"))
      (node (ref "R13") (pin "1") (pinfunction "1_1") (pintype "passive"))
    )
    (net (code "51") (name "Net-(Q8-D)") (class "Default")
      (node (ref "Q8") (pin "3") (pinfunction "D_3") (pintype "passive"))
      (node (ref "R10") (pin "1") (pinfunction "1_1") (pintype "passive"))
    )
    (net (code "52") (name "Net-(Q9-D)") (class "Default")
      (node (ref "Q9") (pin "3") (pinfunction "D_3") (pintype "passive"))
      (node (ref "R18") (pin "1") (pinfunction "1_1") (pintype "passive"))
    )
    (net (code "53") (name "Net-(Q10-D)") (class "Default")
      (node (ref "Q10") (pin "3") (pinfunction "D_3") (pintype "passive"))
      (node (ref "Q9") (pin "1") (pinfunction "G_1") (pintype "passive"))
      (node (ref "R17") (pin "1") (pinfunction "1_1") (pintype "passive"))
    )
    (net (code "54") (name "Net-(Q11-D)") (class "Default")
      (node (ref "Q11") (pin "3") (pinfunction "D_3") (pintype "passive"))
      (node (ref "R20") (pin "1") (pinfunction "1_1") (pintype "passive"))
    )
    (net (code "55") (name "Net-(Q11-G)") (class "Default")
      (node (ref "Q11") (pin "1") (pinfunction "G_1") (pintype "passive"))
      (node (ref "Q12") (pin "3") (pinfunction "D_3") (pintype "passive"))
      (node (ref "R19") (pin "1") (pinfunction "1_1") (pintype "passive"))
    )
    (net (code "56") (name "Net-(Q13-D)") (class "Default")
      (node (ref "Q13") (pin "3") (pinfunction "D_3") (pintype "passive"))
      (node (ref "R24") (pin "1") (pinfunction "1_1") (pintype "passive"))
    )
    (net (code "57") (name "Net-(Q13-G)") (class "Default")
      (node (ref "Q13") (pin "1") (pinfunction "G_1") (pintype "passive"))
      (node (ref "Q14") (pin "3") (pinfunction "D_3") (pintype "passive"))
      (node (ref "R22") (pin "1") (pinfunction "1_1") (pintype "passive"))
    )
    (net (code "58") (name "Net-(R11-Pad1)") (class "Default")
      (node (ref "R11") (pin "1") (pinfunction "1_1") (pintype "passive"))
      (node (ref "S_R") (pin "P") (pinfunction "P_P") (pintype "passive"))
      (node (ref "S_R") (pin "P1") (pinfunction "P_P1") (pintype "passive"))
    )
    (net (code "59") (name "Net-(R17-Pad2)") (class "Default")
      (node (ref "R17") (pin "2") (pinfunction "2_2") (pintype "passive"))
      (node (ref "S1") (pin "P$6") (pinfunction "P$6_P$6") (pintype "bidirectional"))
    )
    (net (code "60") (name "Net-(R18-Pad2)") (class "Default")
      (node (ref "R18") (pin "2") (pinfunction "2_2") (pintype "passive"))
      (node (ref "S1") (pin "P$4") (pinfunction "P$4_P$4") (pintype "bidirectional"))
    )
    (net (code "61") (name "Net-(R19-Pad2)") (class "Default")
      (node (ref "R19") (pin "2") (pinfunction "2_2") (pintype "passive"))
      (node (ref "S2") (pin "P$6") (pinfunction "P$6_P$6") (pintype "bidirectional"))
    )
    (net (code "62") (name "Net-(R20-Pad2)") (class "Default")
      (node (ref "R20") (pin "2") (pinfunction "2_2") (pintype "passive"))
      (node (ref "S2") (pin "P$4") (pinfunction "P$4_P$4") (pintype "bidirectional"))
    )
    (net (code "63") (name "Net-(R21-Pad2)") (class "Default")
      (node (ref "R21") (pin "2") (pinfunction "2_2") (pintype "passive"))
      (node (ref "S2") (pin "P$2") (pinfunction "P$2_P$2") (pintype "bidirectional"))
    )
    (net (code "64") (name "Net-(R22-Pad2)") (class "Default")
      (node (ref "R22") (pin "2") (pinfunction "2_2") (pintype "passive"))
      (node (ref "S3") (pin "P$6") (pinfunction "P$6_P$6") (pintype "bidirectional"))
    )
    (net (code "65") (name "Net-(R23-Pad2)") (class "Default")
      (node (ref "R23") (pin "2") (pinfunction "2_2") (pintype "passive"))
      (node (ref "S1") (pin "P$2") (pinfunction "P$2_P$2") (pintype "bidirectional"))
    )
    (net (code "66") (name "Net-(R24-Pad2)") (class "Default")
      (node (ref "R24") (pin "2") (pinfunction "2_2") (pintype "passive"))
      (node (ref "S3") (pin "P$4") (pinfunction "P$4_P$4") (pintype "bidirectional"))
    )
    (net (code "67") (name "Net-(R25-Pad2)") (class "Default")
      (node (ref "R25") (pin "2") (pinfunction "2_2") (pintype "passive"))
      (node (ref "S3") (pin "P$2") (pinfunction "P$2_P$2") (pintype "bidirectional"))
    )
    (net (code "68") (name "Net-(U$5-ADJ)") (class "Default")
      (node (ref "RSET") (pin "1") (pinfunction "1_1") (pintype "passive"))
      (node (ref "U$5") (pin "4") (pinfunction "ADJ_4") (pintype "passive"))
    )
    (net (code "69") (name "OPT_SWITCH_1") (class "Default")
      (node (ref "Q10") (pin "1") (pinfunction "G_1") (pintype "passive"))
      (node (ref "R23") (pin "1") (pinfunction "1_1") (pintype "passive"))
      (node (ref "U$3") (pin "P$46") (pinfunction "PB1/USB0VBUS_P$46") (pintype "bidirectional"))
    )
    (net (code "70") (name "OPT_SWITCH_2") (class "Default")
      (node (ref "Q12") (pin "1") (pinfunction "G_1") (pintype "passive"))
      (node (ref "R21") (pin "1") (pinfunction "1_1") (pintype "passive"))
      (node (ref "U$3") (pin "P$47") (pinfunction "PB2/I2C0SCL_P$47") (pintype "bidirectional"))
    )
    (net (code "71") (name "OPT_SWITCH_3") (class "Default")
      (node (ref "Q14") (pin "1") (pinfunction "G_1") (pintype "passive"))
      (node (ref "R25") (pin "1") (pinfunction "1_1") (pintype "passive"))
      (node (ref "U$3") (pin "P$48") (pinfunction "PB3/I2C0SDA_P$48") (pintype "bidirectional"))
    )
    (net (code "72") (name "RC_1") (class "Default")
      (node (ref "RC") (pin "P$1") (pinfunction "P$1_P$1") (pintype "bidirectional"))
      (node (ref "U$3") (pin "P$19") (pinfunction "PA2/SSI0CLK_P$19") (pintype "bidirectional"))
    )
    (net (code "73") (name "RC_2") (class "Default")
      (node (ref "RC") (pin "P$2") (pinfunction "P$2_P$2") (pintype "bidirectional"))
      (node (ref "U$3") (pin "P$20") (pinfunction "PA3/SSI0FSS_P$20") (pintype "bidirectional"))
    )
    (net (code "74") (name "RC_3") (class "Default")
      (node (ref "RC") (pin "P$3") (pinfunction "P$3_P$3") (pintype "bidirectional"))
      (node (ref "U$3") (pin "P$21") (pinfunction "PA4/SSI0RX_P$21") (pintype "bidirectional"))
    )
    (net (code "75") (name "RC_4") (class "Default")
      (node (ref "RC") (pin "P$4") (pinfunction "P$4_P$4") (pintype "bidirectional"))
      (node (ref "U$3") (pin "P$22") (pinfunction "PA5/SSI0TX_P$22") (pintype "bidirectional"))
    )
    (net (code "76") (name "RC_5") (class "Default")
      (node (ref "RC") (pin "P$5") (pinfunction "P$5_P$5") (pintype "bidirectional"))
      (node (ref "U$3") (pin "P$23") (pinfunction "PA6_P$23") (pintype "bidirectional"))
    )
    (net (code "77") (name "RC_6") (class "Default")
      (node (ref "RC") (pin "P$6") (pinfunction "P$6_P$6") (pintype "bidirectional"))
      (node (ref "U$3") (pin "P$24") (pinfunction "PA7_P$24") (pintype "bidirectional"))
    )
    (net (code "78") (name "RESET") (class "Default")
      (node (ref "C10") (pin "1") (pinfunction "1_1") (pintype "passive"))
      (node (ref "C4") (pin "1") (pinfunction "1_1") (pintype "passive"))
      (node (ref "R11") (pin "2") (pinfunction "2_2") (pintype "passive"))
      (node (ref "R9") (pin "1") (pinfunction "1_1") (pintype "passive"))
      (node (ref "SV1") (pin "3") (pinfunction "RESET_3") (pintype "passive"))
      (node (ref "U$2") (pin "10") (pinfunction "RESET_10") (pintype "bidirectional"))
      (node (ref "U$3") (pin "P$38") (pinfunction "~{RST}_P$38") (pintype "bidirectional"))
      (node (ref "U1") (pin "P$29") (pinfunction "RESET_P$29") (pintype "bidirectional"))
    )
    (net (code "79") (name "RS-232_RX1") (class "Default")
      (node (ref "CONV") (pin "P$8") (pinfunction "RIN_P$8") (pintype "input"))
      (node (ref "J7") (pin "3") (pinfunction "P$3_3") (pintype "bidirectional"))
    )
    (net (code "80") (name "RS-232_TX1") (class "Default")
      (node (ref "CONV") (pin "P$13") (pinfunction "DOUT_P$13") (pintype "output"))
      (node (ref "J7") (pin "2") (pinfunction "P$2_2") (pintype "bidirectional"))
    )
    (net (code "81") (name "RX1_3V3") (class "Default")
      (node (ref "CONV") (pin "P$9") (pinfunction "ROUT_P$9") (pintype "output"))
      (node (ref "U$3") (pin "P$17") (pinfunction "PA0/U0RX_P$17") (pintype "bidirectional"))
    )
    (net (code "82") (name "SCK") (class "Default")
      (node (ref "SV1") (pin "2") (pinfunction "SCK_2") (pintype "passive"))
      (node (ref "U1") (pin "P$17") (pinfunction "(SCK)PB5_P$17") (pintype "bidirectional"))
    )
    (net (code "83") (name "SCL_3V3") (class "Default")
      (node (ref "I2C_1") (pin "2") (pinfunction "P$2_2") (pintype "bidirectional"))
      (node (ref "I2C_2") (pin "2") (pinfunction "P$2_2") (pintype "bidirectional"))
      (node (ref "R8") (pin "2") (pinfunction "2_2") (pintype "passive"))
      (node (ref "U$3") (pin "P$61") (pinfunction "PD0_P$61") (pintype "bidirectional"))
      (node (ref "U1") (pin "P$28") (pinfunction "(ADC5)PC5_P$28") (pintype "bidirectional"))
    )
    (net (code "84") (name "SDA_3V3") (class "Default")
      (node (ref "I2C_1") (pin "3") (pinfunction "P$3_3") (pintype "bidirectional"))
      (node (ref "I2C_2") (pin "3") (pinfunction "P$3_3") (pintype "bidirectional"))
      (node (ref "R7") (pin "2") (pinfunction "2_2") (pintype "passive"))
      (node (ref "U$3") (pin "P$62") (pinfunction "PD1_P$62") (pintype "bidirectional"))
      (node (ref "U1") (pin "P$27") (pinfunction "(ADC4)PC4_P$27") (pintype "bidirectional"))
    )
    (net (code "85") (name "TX1_3V3") (class "Default")
      (node (ref "CONV") (pin "P$11") (pinfunction "DIN_P$11") (pintype "input"))
      (node (ref "U$3") (pin "P$18") (pinfunction "PA1/U0TX_P$18") (pintype "bidirectional"))
    )
    (net (code "86") (name "T_BLUE_LED") (class "Default")
      (node (ref "Q2") (pin "1") (pinfunction "G_1") (pintype "passive"))
      (node (ref "U$3") (pin "P$30") (pinfunction "PF2_P$30") (pintype "bidirectional"))
    )
    (net (code "87") (name "T_GREEN_LED") (class "Default")
      (node (ref "Q3") (pin "1") (pinfunction "G_1") (pintype "passive"))
      (node (ref "U$3") (pin "P$31") (pinfunction "PF3_P$31") (pintype "bidirectional"))
    )
    (net (code "88") (name "T_OSC0") (class "Default")
      (node (ref "C18") (pin "1") (pinfunction "1_1") (pintype "passive"))
      (node (ref "U$1") (pin "3") (pinfunction "2_3") (pintype "bidirectional"))
      (node (ref "U$3") (pin "P$40") (pinfunction "OSC0_P$40") (pintype "bidirectional"))
    )
    (net (code "89") (name "T_OSC1") (class "Default")
      (node (ref "C17") (pin "1") (pinfunction "1_1") (pintype "passive"))
      (node (ref "U$1") (pin "1") (pinfunction "1_1") (pintype "bidirectional"))
      (node (ref "U$3") (pin "P$41") (pinfunction "OSC1_P$41") (pintype "bidirectional"))
    )
    (net (code "90") (name "T_RED_LED") (class "Default")
      (node (ref "Q4") (pin "1") (pinfunction "G_1") (pintype "passive"))
      (node (ref "U$3") (pin "P$29") (pinfunction "PF1_P$29") (pintype "bidirectional"))
    )
    (net (code "91") (name "T_VDDC") (class "Default")
      (node (ref "C1") (pin "1") (pinfunction "1_1") (pintype "passive"))
      (node (ref "C12") (pin "1") (pinfunction "1_1") (pintype "passive"))
      (node (ref "C13") (pin "1") (pinfunction "1_1") (pintype "passive"))
      (node (ref "C14") (pin "1") (pinfunction "1_1") (pintype "passive"))
      (node (ref "U$3") (pin "P$25") (pinfunction "VDDC_P$25") (pintype "bidirectional"))
      (node (ref "U$3") (pin "P$56") (pinfunction "VDDC_P$56") (pintype "bidirectional"))
    )
    (net (code "92") (name "V_BATT") (class "Default")
      (node (ref "C26") (pin "1") (pinfunction "1_1") (pintype "passive"))
      (node (ref "C3") (pin "1") (pinfunction "1_1") (pintype "passive"))
      (node (ref "C31") (pin "+") (pinfunction "+_+") (pintype "passive"))
      (node (ref "Q21") (pin "S1") (pinfunction "S1_S1") (pintype "passive"))
      (node (ref "Q21") (pin "S2") (pinfunction "S1_S2") (pintype "passive"))
      (node (ref "Q21") (pin "S3") (pinfunction "S1_S3") (pintype "passive"))
      (node (ref "Q22") (pin "S1") (pinfunction "S1_S1") (pintype "passive"))
      (node (ref "Q22") (pin "S2") (pinfunction "S1_S2") (pintype "passive"))
      (node (ref "Q22") (pin "S3") (pinfunction "S1_S3") (pintype "passive"))
      (node (ref "Q23") (pin "S1") (pinfunction "S1_S1") (pintype "passive"))
      (node (ref "Q23") (pin "S2") (pinfunction "S1_S2") (pintype "passive"))
      (node (ref "Q23") (pin "S3") (pinfunction "S1_S3") (pintype "passive"))
      (node (ref "Q24") (pin "S1") (pinfunction "S1_S1") (pintype "passive"))
      (node (ref "Q24") (pin "S2") (pinfunction "S1_S2") (pintype "passive"))
      (node (ref "Q24") (pin "S3") (pinfunction "S1_S3") (pintype "passive"))
      (node (ref "Q5") (pin "S1") (pinfunction "S1_S1") (pintype "passive"))
      (node (ref "Q5") (pin "S2") (pinfunction "S1_S2") (pintype "passive"))
      (node (ref "Q5") (pin "S3") (pinfunction "S1_S3") (pintype "passive"))
      (node (ref "R1") (pin "2") (pinfunction "2_2") (pintype "passive"))
      (node (ref "U$5") (pin "2") (pinfunction "V_I_2") (pintype "input"))
      (node (ref "V_BATT1") (pin "VCC-1") (pinfunction "VCC_VCC-1") (pintype "bidirectional"))
      (node (ref "V_BATT1") (pin "VCC-2") (pinfunction "VCC_VCC-2") (pintype "bidirectional"))
    )
    (net (code "93") (name "unconnected-(CONV-INVLAID-PadP$10)") (class "Default")
      (node (ref "CONV") (pin "P$10") (pinfunction "INVLAID_P$10") (pintype "output"))
    )
    (net (code "94") (name "unconnected-(S1-PadP$3)") (class "Default")
      (node (ref "S1") (pin "P$3") (pinfunction "P$3_P$3") (pintype "bidirectional"))
    )
    (net (code "95") (name "unconnected-(S2-PadP$3)") (class "Default")
      (node (ref "S2") (pin "P$3") (pinfunction "P$3_P$3") (pintype "bidirectional"))
    )
    (net (code "96") (name "unconnected-(S3-PadP$3)") (class "Default")
      (node (ref "S3") (pin "P$3") (pinfunction "P$3_P$3") (pintype "bidirectional"))
    )
    (net (code "97") (name "unconnected-(U$2-VCC-Pad1)") (class "Default")
      (node (ref "U$2") (pin "1") (pinfunction "VCC_1") (pintype "bidirectional"))
    )
    (net (code "98") (name "unconnected-(U$3-PB0{slash}USB0ID-PadP$45)") (class "Default")
      (node (ref "U$3") (pin "P$45") (pinfunction "PB0/USB0ID_P$45") (pintype "bidirectional"))
    )
    (net (code "99") (name "unconnected-(U$3-PB4-PadP$58)") (class "Default")
      (node (ref "U$3") (pin "P$58") (pinfunction "PB4_P$58") (pintype "bidirectional"))
    )
    (net (code "100") (name "unconnected-(U$3-PB5-PadP$57)") (class "Default")
      (node (ref "U$3") (pin "P$57") (pinfunction "PB5_P$57") (pintype "bidirectional"))
    )
    (net (code "101") (name "unconnected-(U$3-PB7-PadP$4)") (class "Default")
      (node (ref "U$3") (pin "P$4") (pinfunction "PB7_P$4") (pintype "bidirectional"))
    )
    (net (code "102") (name "unconnected-(U$3-PC4-PadP$16)") (class "Default")
      (node (ref "U$3") (pin "P$16") (pinfunction "PC4_P$16") (pintype "bidirectional"))
    )
    (net (code "103") (name "unconnected-(U$3-PC5-PadP$15)") (class "Default")
      (node (ref "U$3") (pin "P$15") (pinfunction "PC5_P$15") (pintype "bidirectional"))
    )
    (net (code "104") (name "unconnected-(U$3-PC6-PadP$14)") (class "Default")
      (node (ref "U$3") (pin "P$14") (pinfunction "PC6_P$14") (pintype "bidirectional"))
    )
    (net (code "105") (name "unconnected-(U$3-PC7-PadP$13)") (class "Default")
      (node (ref "U$3") (pin "P$13") (pinfunction "PC7_P$13") (pintype "bidirectional"))
    )
    (net (code "106") (name "unconnected-(U$3-PD2-PadP$63)") (class "Default")
      (node (ref "U$3") (pin "P$63") (pinfunction "PD2_P$63") (pintype "bidirectional"))
    )
    (net (code "107") (name "unconnected-(U$3-PD3-PadP$64)") (class "Default")
      (node (ref "U$3") (pin "P$64") (pinfunction "PD3_P$64") (pintype "bidirectional"))
    )
    (net (code "108") (name "unconnected-(U$3-PD4-PadP$43)") (class "Default")
      (node (ref "U$3") (pin "P$43") (pinfunction "PD4_P$43") (pintype "bidirectional"))
    )
    (net (code "109") (name "unconnected-(U$3-PD5-PadP$44)") (class "Default")
      (node (ref "U$3") (pin "P$44") (pinfunction "PD5_P$44") (pintype "bidirectional"))
    )
    (net (code "110") (name "unconnected-(U$3-PD6-PadP$53)") (class "Default")
      (node (ref "U$3") (pin "P$53") (pinfunction "PD6_P$53") (pintype "bidirectional"))
    )
    (net (code "111") (name "unconnected-(U$3-PD7-PadP$10)") (class "Default")
      (node (ref "U$3") (pin "P$10") (pinfunction "PD7_P$10") (pintype "bidirectional"))
    )
    (net (code "112") (name "unconnected-(U$3-PF0-PadP$28)") (class "Default")
      (node (ref "U$3") (pin "P$28") (pinfunction "PF0_P$28") (pintype "bidirectional"))
    )
    (net (code "113") (name "unconnected-(U$3-PF4-PadP$5)") (class "Default")
      (node (ref "U$3") (pin "P$5") (pinfunction "PF4_P$5") (pintype "bidirectional"))
    )
    (net (code "114") (name "unconnected-(U$3-XOSC1-PadP$36)") (class "Default")
      (node (ref "U$3") (pin "P$36") (pinfunction "XOSC1_P$36") (pintype "bidirectional"))
    )
    (net (code "115") (name "unconnected-(U$3-~{HIB}-PadP$33)") (class "Default")
      (node (ref "U$3") (pin "P$33") (pinfunction "~{HIB}_P$33") (pintype "bidirectional"))
    )
    (net (code "116") (name "unconnected-(U$4-PadP$3)") (class "Default")
      (node (ref "U$4") (pin "P$3") (pinfunction "P$3_P$3") (pintype "bidirectional"))
    )
    (net (code "117") (name "unconnected-(U$4-PadP$4)") (class "Default")
      (node (ref "U$4") (pin "P$4") (pinfunction "P$4_P$4") (pintype "bidirectional"))
    )
    (net (code "118") (name "unconnected-(U1-(ADC2)PC2-PadP$25)") (class "Default")
      (node (ref "U1") (pin "P$25") (pinfunction "(ADC2)PC2_P$25") (pintype "bidirectional"))
    )
    (net (code "119") (name "unconnected-(U1-(ADC3)PC3-PadP$26)") (class "Default")
      (node (ref "U1") (pin "P$26") (pinfunction "(ADC3)PC3_P$26") (pintype "bidirectional"))
    )
    (net (code "120") (name "unconnected-(U1-(AIN0)PD6-PadP$10)") (class "Default")
      (node (ref "U1") (pin "P$10") (pinfunction "(AIN0)PD6_P$10") (pintype "bidirectional"))
    )
    (net (code "121") (name "unconnected-(U1-(INT0)PD2-PadP$32)") (class "Default")
      (node (ref "U1") (pin "P$32") (pinfunction "(INT0)PD2_P$32") (pintype "bidirectional"))
    )
    (net (code "122") (name "unconnected-(U1-(INT1)PD3-PadP$1)") (class "Default")
      (node (ref "U1") (pin "P$1") (pinfunction "(INT1)PD3_P$1") (pintype "bidirectional"))
    )
    (net (code "123") (name "unconnected-(U1-(RXD)PD0-PadP$30)") (class "Default")
      (node (ref "U1") (pin "P$30") (pinfunction "(RXD)PD0_P$30") (pintype "bidirectional"))
    )
    (net (code "124") (name "unconnected-(U1-(SS)PB2-PadP$14)") (class "Default")
      (node (ref "U1") (pin "P$14") (pinfunction "(SS)PB2_P$14") (pintype "bidirectional"))
    )
    (net (code "125") (name "unconnected-(U1-(T1)PD5-PadP$9)") (class "Default")
      (node (ref "U1") (pin "P$9") (pinfunction "(T1)PD5_P$9") (pintype "bidirectional"))
    )
    (net (code "126") (name "unconnected-(U1-(TXD)PD1-PadP$31)") (class "Default")
      (node (ref "U1") (pin "P$31") (pinfunction "(TXD)PD1_P$31") (pintype "bidirectional"))
    )
    (net (code "127") (name "unconnected-(U1-ADC6-PadP$19)") (class "Default")
      (node (ref "U1") (pin "P$19") (pinfunction "ADC6_P$19") (pintype "bidirectional"))
    )
    (net (code "128") (name "unconnected-(U1-ADC7-PadP$22)") (class "Default")
      (node (ref "U1") (pin "P$22") (pinfunction "ADC7_P$22") (pintype "bidirectional"))
    )
  )
)
